# Educ-8.net
KiCad netlist of a schematic drawn in EAGLE
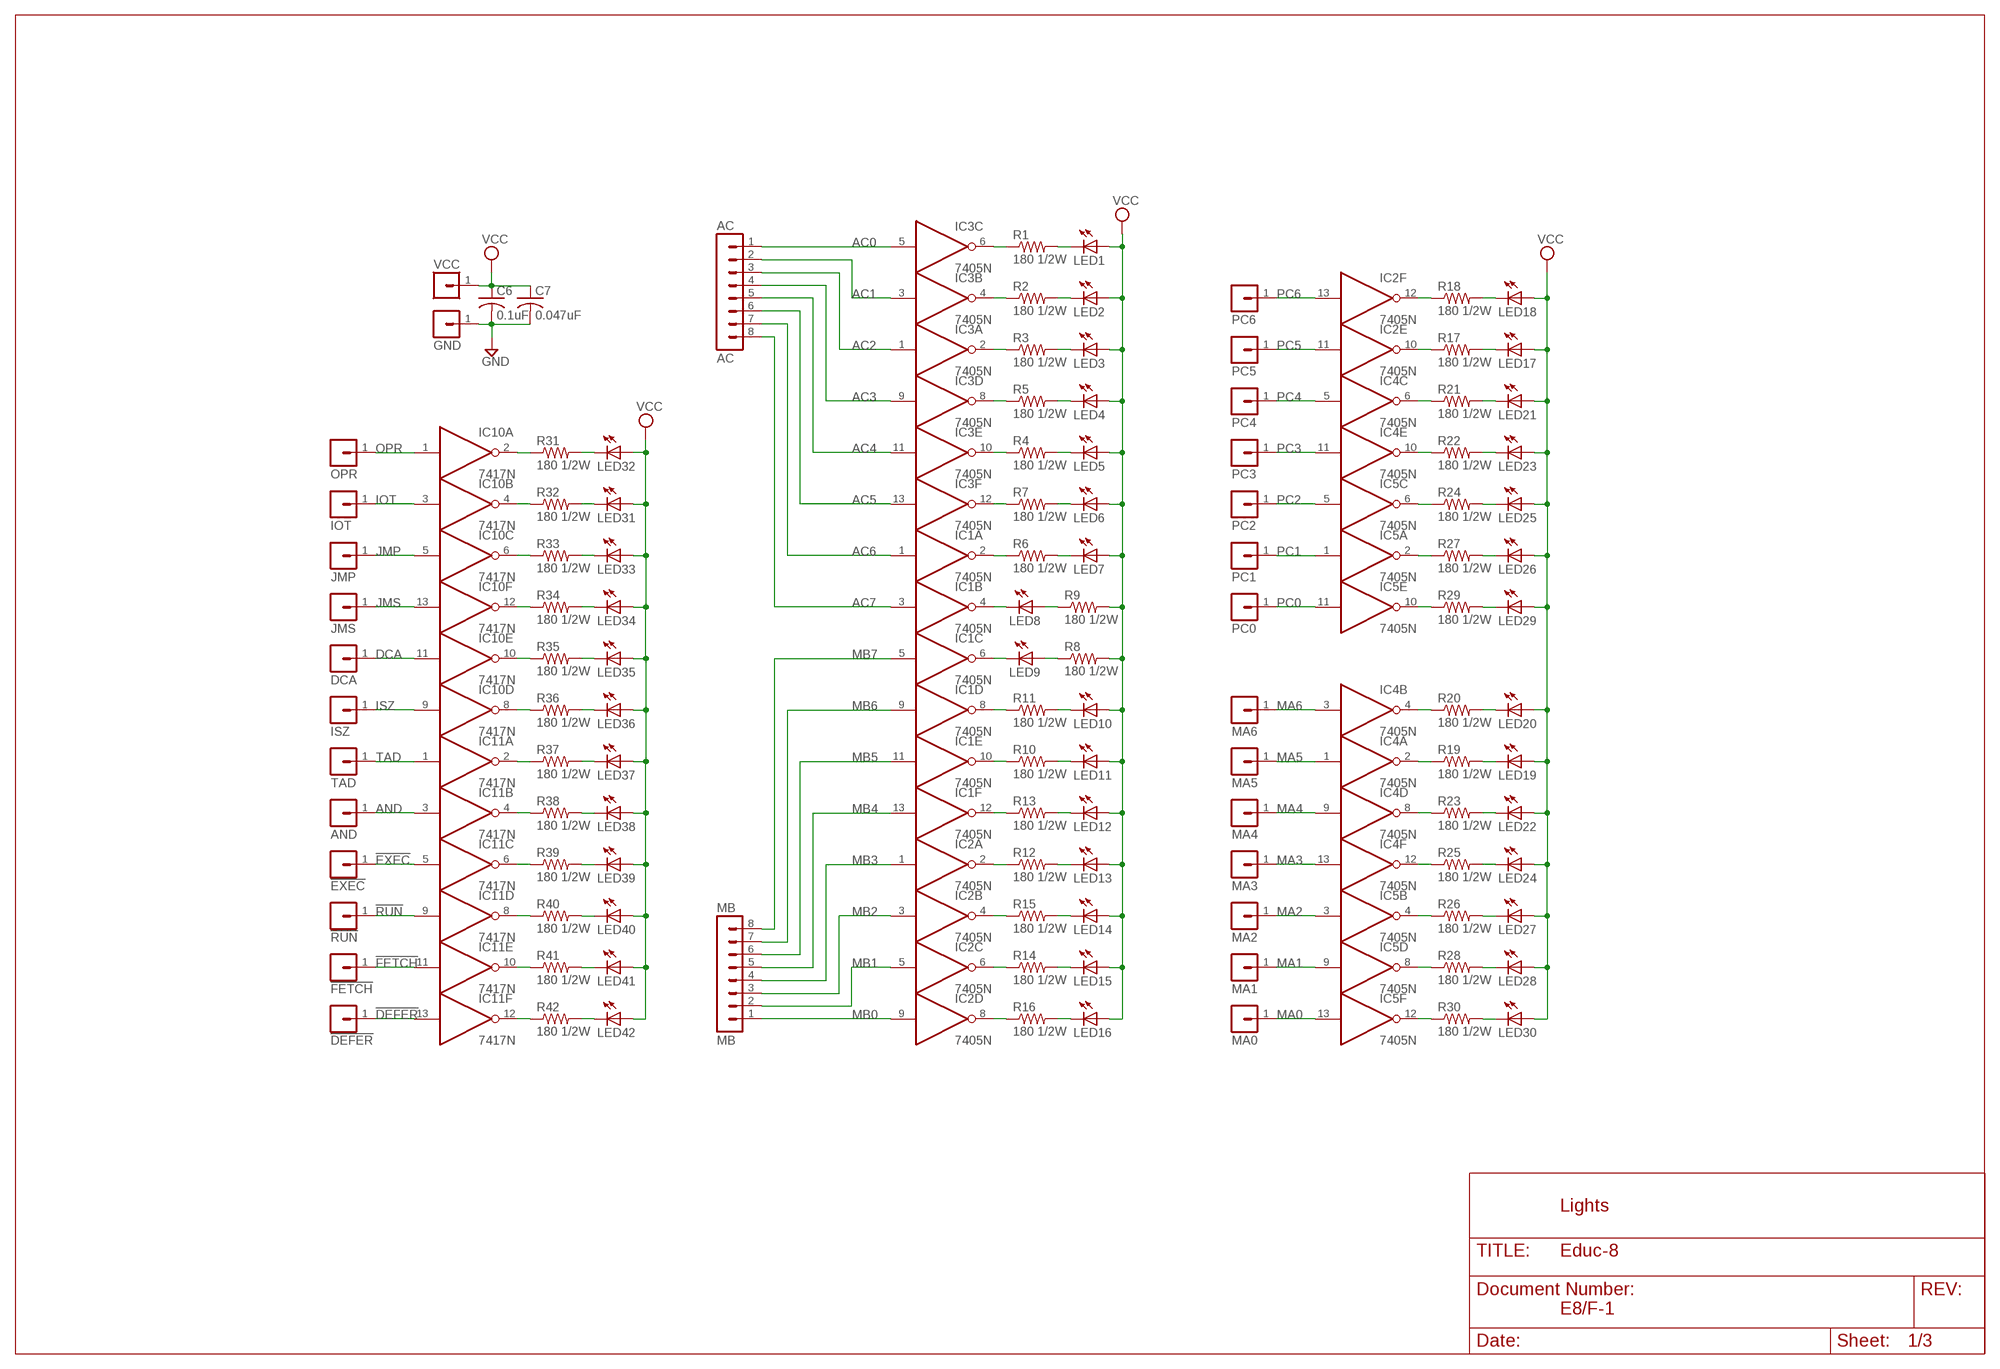
[diagram p0: schematic, sheet 1]
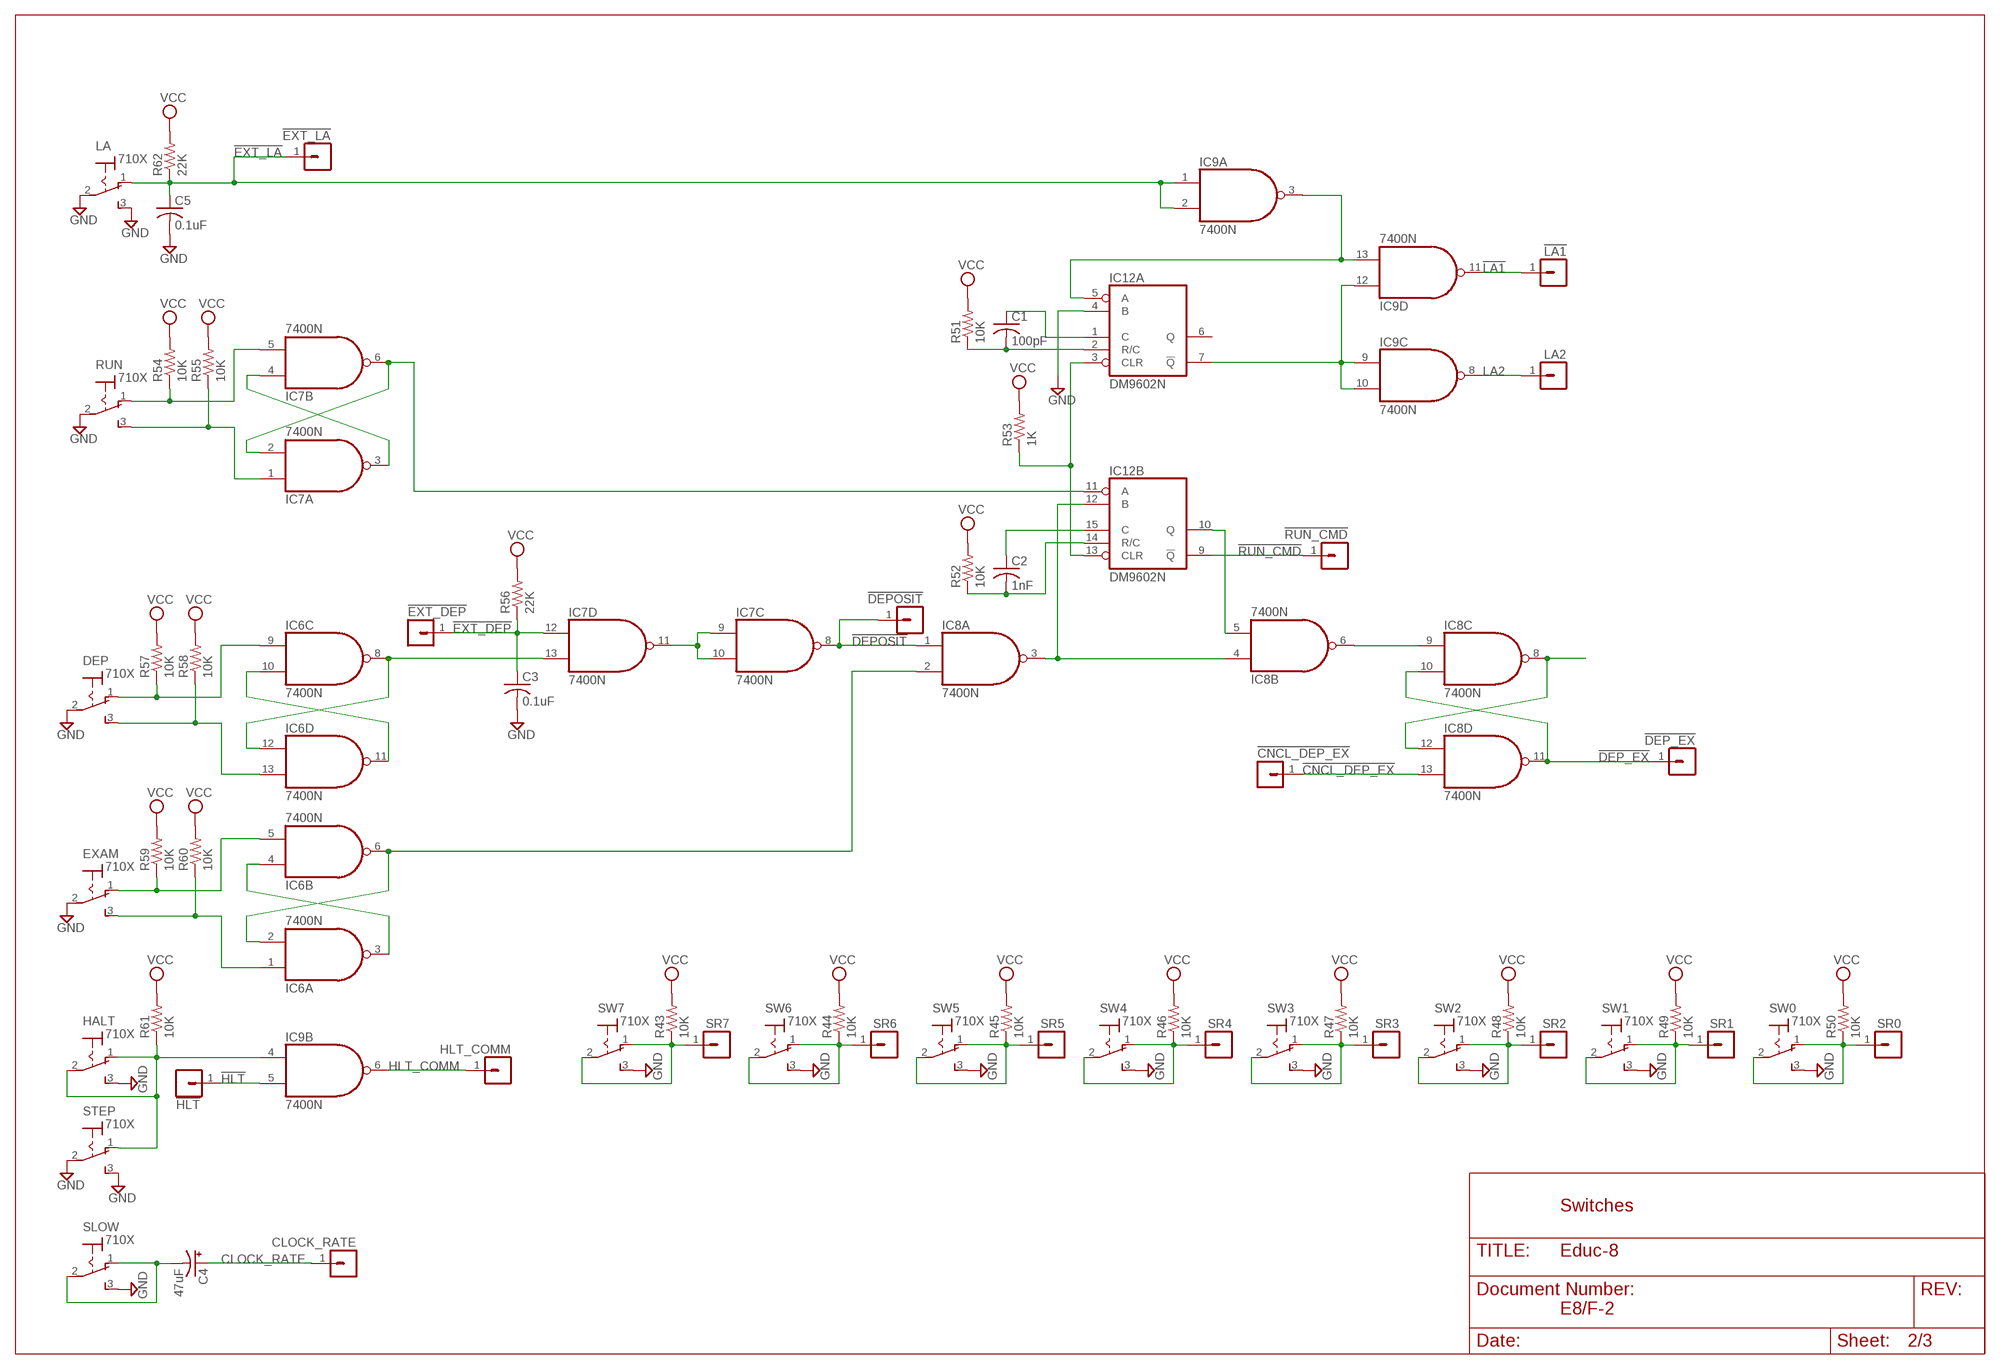
[diagram p1: schematic, sheet 2]
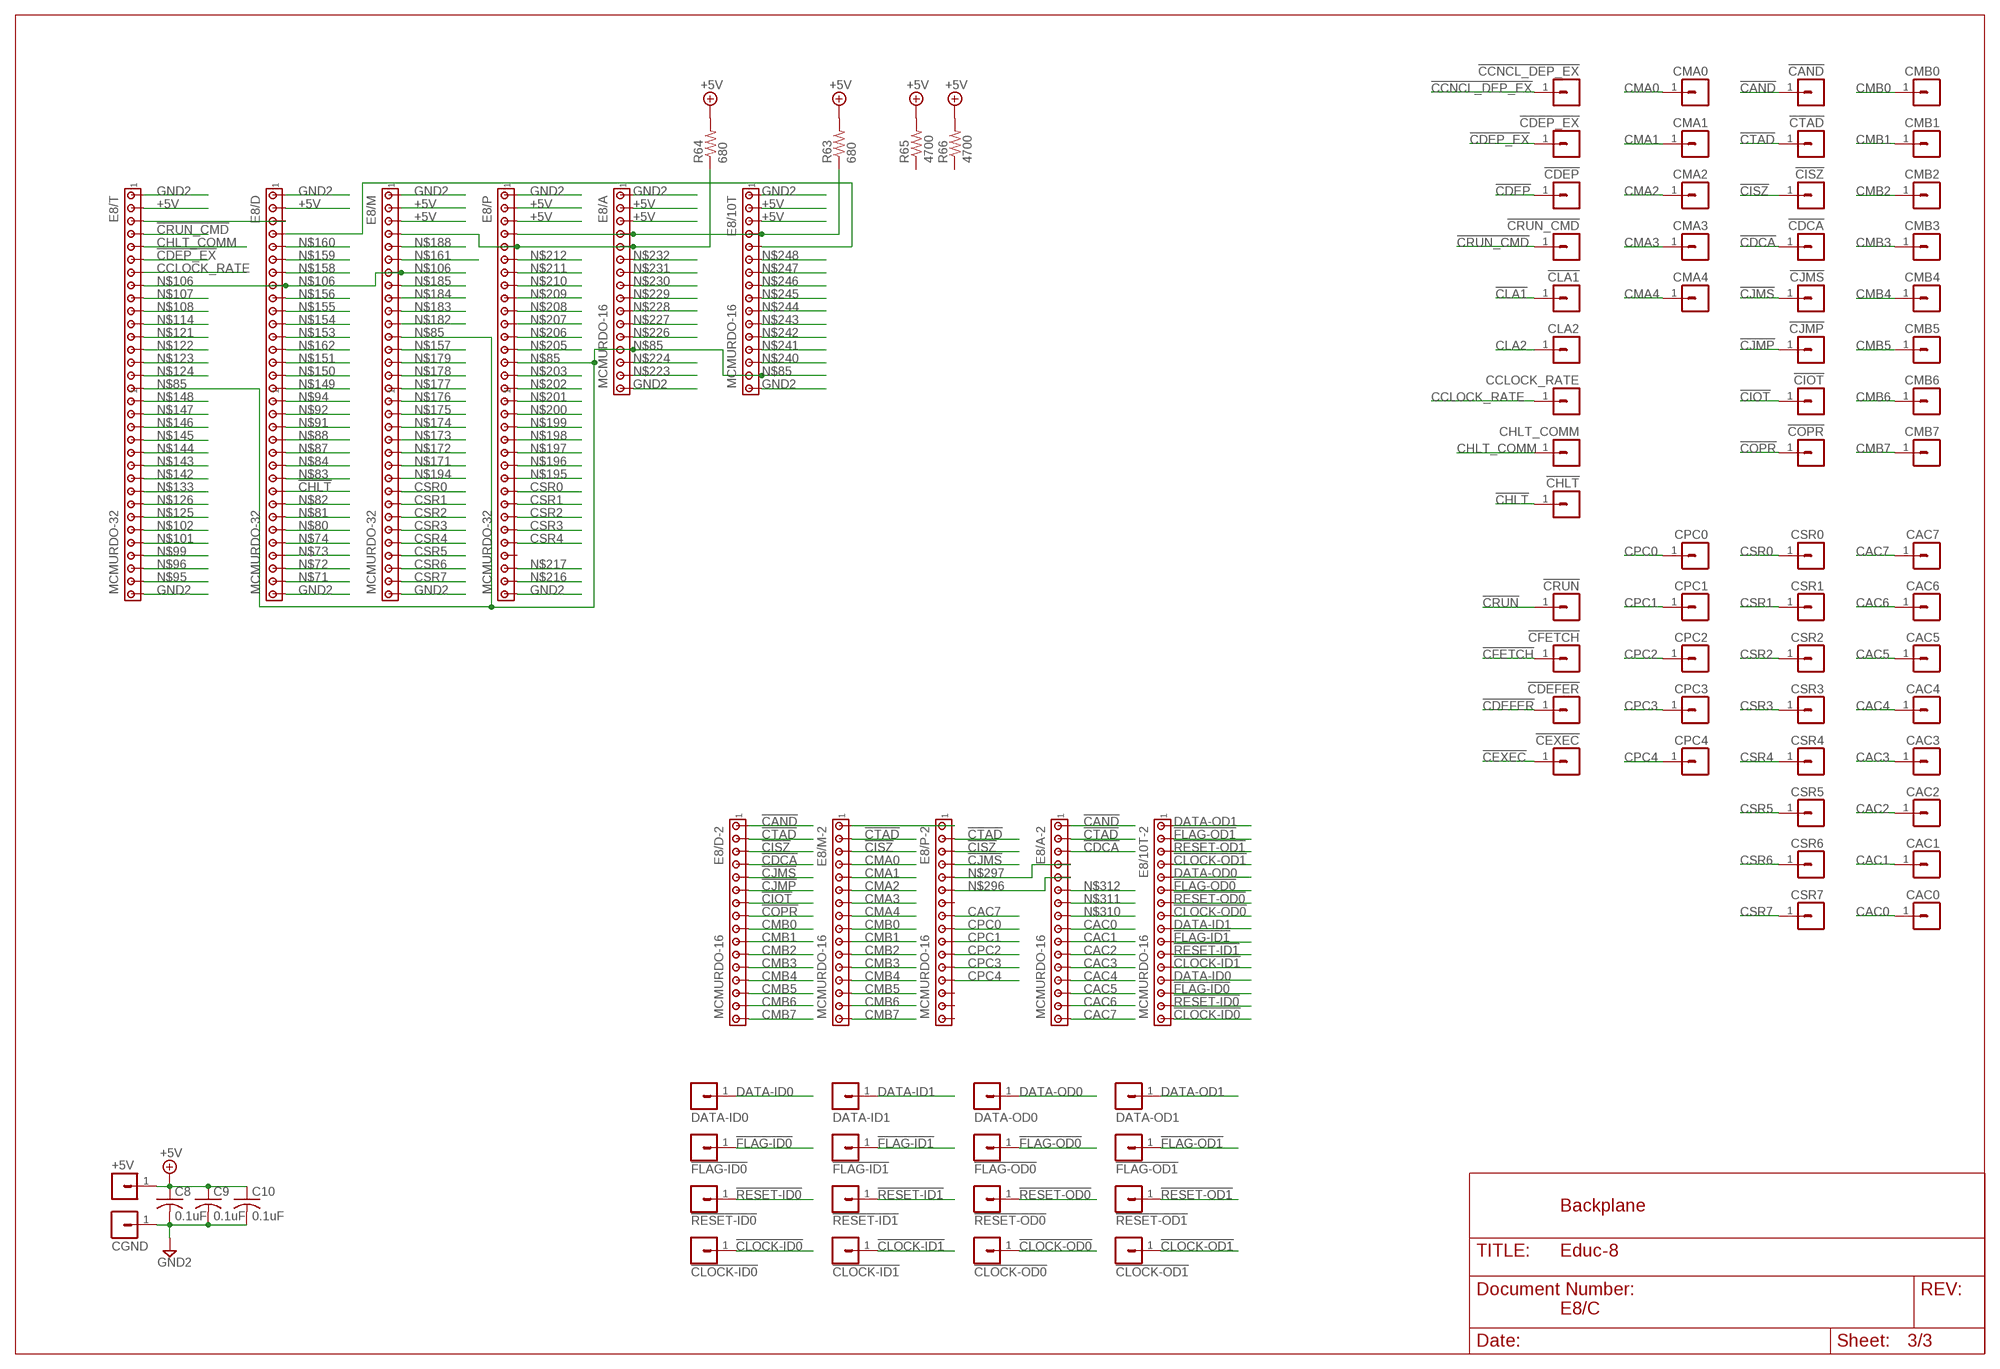
[diagram p2: schematic, sheet 3]

(export (version "E")
  (design (tool "Eeschema 10.0.6"))
  (components
    (comp (ref "!CNCL_DEP_EX")
      (value "MA01-1")
      (footprint "eagle-import:MA01-1")
      (libsource (lib "eagle-import") (part "MA01-1"))
    )
    (comp (ref "!DEPOSIT")
      (value "MA01-1")
      (footprint "eagle-import:MA01-1")
      (libsource (lib "eagle-import") (part "MA01-1"))
    )
    (comp (ref "!DEP_EX")
      (value "MA01-1")
      (footprint "eagle-import:MA01-1")
      (libsource (lib "eagle-import") (part "MA01-1"))
    )
    (comp (ref "!EXT_DEP")
      (value "MA01-1")
      (footprint "eagle-import:MA01-1")
      (libsource (lib "eagle-import") (part "MA01-1"))
    )
    (comp (ref "!EXT_LA")
      (value "MA01-1")
      (footprint "eagle-import:MA01-1")
      (libsource (lib "eagle-import") (part "MA01-1"))
    )
    (comp (ref "!HLT")
      (value "MA01-1")
      (footprint "eagle-import:MA01-1")
      (libsource (lib "eagle-import") (part "MA01-1"))
    )
    (comp (ref "!LA1")
      (value "MA01-1")
      (footprint "eagle-import:MA01-1")
      (libsource (lib "eagle-import") (part "MA01-1"))
    )
    (comp (ref "!RUN_CMD")
      (value "MA01-1")
      (footprint "eagle-import:MA01-1")
      (libsource (lib "eagle-import") (part "MA01-1"))
    )
    (comp (ref "C1")
      (value "100pF")
      (footprint "eagle-import:C075-032X103")
      (libsource (lib "eagle-import") (part "C-US075-032X103"))
    )
    (comp (ref "C2")
      (value "1nF")
      (footprint "eagle-import:C075-032X103")
      (libsource (lib "eagle-import") (part "C-US075-032X103"))
    )
    (comp (ref "C3")
      (value "0.1uF")
      (footprint "eagle-import:C063-025X075")
      (libsource (lib "eagle-import") (part "C-US"))
    )
    (comp (ref "C4")
      (value "47uF")
      (footprint "eagle-import:B45181C")
      (libsource (lib "eagle-import") (part "CPOL-USB45181C"))
    )
    (comp (ref "C5")
      (value "0.1uF")
      (footprint "eagle-import:C075-032X103")
      (libsource (lib "eagle-import") (part "C-US075-032X103"))
    )
    (comp (ref "CLOCK_RATE")
      (value "MA01-1")
      (footprint "eagle-import:MA01-1")
      (libsource (lib "eagle-import") (part "MA01-1"))
    )
    (comp (ref "DEP")
      (value "710X")
      (footprint "eagle-import:7109")
      (libsource (lib "eagle-import") (part "710X"))
    )
    (comp (ref "EXAM")
      (value "710X")
      (footprint "eagle-import:7109")
      (libsource (lib "eagle-import") (part "710X"))
    )
    (comp (ref "HALT")
      (value "710X")
      (footprint "eagle-import:7109")
      (libsource (lib "eagle-import") (part "710X"))
    )
    (comp (ref "HLT_COMM")
      (value "MA01-1")
      (footprint "eagle-import:MA01-1")
      (libsource (lib "eagle-import") (part "MA01-1"))
    )
    (comp (ref "IC6")
      (value "7400N")
      (footprint "eagle-import:DIL14")
      (libsource (lib "eagle-import") (part "7400N"))
    )
    (comp (ref "IC7")
      (value "7400N")
      (footprint "eagle-import:DIL14")
      (libsource (lib "eagle-import") (part "7400N"))
    )
    (comp (ref "IC8")
      (value "7400N")
      (footprint "eagle-import:DIL14")
      (libsource (lib "eagle-import") (part "7400N"))
    )
    (comp (ref "IC9")
      (value "7400N")
      (footprint "eagle-import:DIL14")
      (libsource (lib "eagle-import") (part "7400N"))
    )
    (comp (ref "IC12")
      (value "DM9602N")
      (footprint "eagle-import:DIL16")
      (libsource (lib "eagle-import") (part "DM9602N"))
    )
    (comp (ref "LA")
      (value "710X")
      (footprint "eagle-import:7109")
      (libsource (lib "eagle-import") (part "710X"))
    )
    (comp (ref "LA2")
      (value "MA01-1")
      (footprint "eagle-import:MA01-1")
      (libsource (lib "eagle-import") (part "MA01-1"))
    )
    (comp (ref "R43")
      (value "10K")
      (footprint "eagle-import:0207_12")
      (libsource (lib "eagle-import") (part "rcl_R-US_0207/12"))
    )
    (comp (ref "R44")
      (value "10K")
      (footprint "eagle-import:0207_12")
      (libsource (lib "eagle-import") (part "rcl_R-US_0207/12"))
    )
    (comp (ref "R45")
      (value "10K")
      (footprint "eagle-import:0207_12")
      (libsource (lib "eagle-import") (part "rcl_R-US_0207/12"))
    )
    (comp (ref "R46")
      (value "10K")
      (footprint "eagle-import:0207_12")
      (libsource (lib "eagle-import") (part "rcl_R-US_0207/12"))
    )
    (comp (ref "R47")
      (value "10K")
      (footprint "eagle-import:0207_12")
      (libsource (lib "eagle-import") (part "rcl_R-US_0207/12"))
    )
    (comp (ref "R48")
      (value "10K")
      (footprint "eagle-import:0207_12")
      (libsource (lib "eagle-import") (part "rcl_R-US_0207/12"))
    )
    (comp (ref "R49")
      (value "10K")
      (footprint "eagle-import:0207_12")
      (libsource (lib "eagle-import") (part "rcl_R-US_0207/12"))
    )
    (comp (ref "R50")
      (value "10K")
      (footprint "eagle-import:0207_12")
      (libsource (lib "eagle-import") (part "rcl_R-US_0207/12"))
    )
    (comp (ref "R51")
      (value "10K")
      (footprint "eagle-import:0207_10")
      (libsource (lib "eagle-import") (part "rcl_R-US_0207/10"))
    )
    (comp (ref "R52")
      (value "10K")
      (footprint "eagle-import:0207_15")
      (libsource (lib "eagle-import") (part "rcl_R-US_0207/15"))
    )
    (comp (ref "R53")
      (value "1K")
      (footprint "eagle-import:0204_6")
      (libsource (lib "eagle-import") (part "R-US_0204/6"))
    )
    (comp (ref "R54")
      (value "10K")
      (footprint "eagle-import:0207_13")
      (libsource (lib "eagle-import") (part "R-US_0207/13"))
    )
    (comp (ref "R55")
      (value "10K")
      (footprint "eagle-import:0207_13")
      (libsource (lib "eagle-import") (part "R-US_0207/13"))
    )
    (comp (ref "R56")
      (value "22K")
      (footprint "eagle-import:0207_10")
      (libsource (lib "eagle-import") (part "R-US_0207/10"))
    )
    (comp (ref "R57")
      (value "10K")
      (footprint "eagle-import:0207_13")
      (libsource (lib "eagle-import") (part "R-US_0207/13"))
    )
    (comp (ref "R58")
      (value "10K")
      (footprint "eagle-import:0207_13")
      (libsource (lib "eagle-import") (part "R-US_0207/13"))
    )
    (comp (ref "R59")
      (value "10K")
      (footprint "eagle-import:0207_13")
      (libsource (lib "eagle-import") (part "R-US_0207/13"))
    )
    (comp (ref "R60")
      (value "10K")
      (footprint "eagle-import:0207_13")
      (libsource (lib "eagle-import") (part "R-US_0207/13"))
    )
    (comp (ref "R61")
      (value "10K")
      (footprint "eagle-import:0207_22")
      (libsource (lib "eagle-import") (part "R-US_0207/22"))
    )
    (comp (ref "R62")
      (value "22K")
      (footprint "eagle-import:0207_13")
      (libsource (lib "eagle-import") (part "R-US_0207/13"))
    )
    (comp (ref "RUN")
      (value "710X")
      (footprint "eagle-import:7109")
      (libsource (lib "eagle-import") (part "710X"))
    )
    (comp (ref "SLOW")
      (value "710X")
      (footprint "eagle-import:7109")
      (libsource (lib "eagle-import") (part "710X"))
    )
    (comp (ref "SR0")
      (value "MA01-1")
      (footprint "eagle-import:MA01-1")
      (libsource (lib "eagle-import") (part "MA01-1"))
    )
    (comp (ref "SR1")
      (value "MA01-1")
      (footprint "eagle-import:MA01-1")
      (libsource (lib "eagle-import") (part "MA01-1"))
    )
    (comp (ref "SR2")
      (value "MA01-1")
      (footprint "eagle-import:MA01-1")
      (libsource (lib "eagle-import") (part "MA01-1"))
    )
    (comp (ref "SR3")
      (value "MA01-1")
      (footprint "eagle-import:MA01-1")
      (libsource (lib "eagle-import") (part "MA01-1"))
    )
    (comp (ref "SR4")
      (value "MA01-1")
      (footprint "eagle-import:MA01-1")
      (libsource (lib "eagle-import") (part "MA01-1"))
    )
    (comp (ref "SR5")
      (value "MA01-1")
      (footprint "eagle-import:MA01-1")
      (libsource (lib "eagle-import") (part "MA01-1"))
    )
    (comp (ref "SR6")
      (value "MA01-1")
      (footprint "eagle-import:MA01-1")
      (libsource (lib "eagle-import") (part "MA01-1"))
    )
    (comp (ref "SR7")
      (value "MA01-1")
      (footprint "eagle-import:MA01-1")
      (libsource (lib "eagle-import") (part "MA01-1"))
    )
    (comp (ref "STEP")
      (value "710X")
      (footprint "eagle-import:7109")
      (libsource (lib "eagle-import") (part "710X"))
    )
    (comp (ref "SW0")
      (value "710X")
      (footprint "eagle-import:7109")
      (libsource (lib "eagle-import") (part "710X"))
    )
    (comp (ref "SW1")
      (value "710X")
      (footprint "eagle-import:7109")
      (libsource (lib "eagle-import") (part "710X"))
    )
    (comp (ref "SW2")
      (value "710X")
      (footprint "eagle-import:7109")
      (libsource (lib "eagle-import") (part "710X"))
    )
    (comp (ref "SW3")
      (value "710X")
      (footprint "eagle-import:7109")
      (libsource (lib "eagle-import") (part "710X"))
    )
    (comp (ref "SW4")
      (value "710X")
      (footprint "eagle-import:7109")
      (libsource (lib "eagle-import") (part "710X"))
    )
    (comp (ref "SW5")
      (value "710X")
      (footprint "eagle-import:7109")
      (libsource (lib "eagle-import") (part "710X"))
    )
    (comp (ref "SW6")
      (value "710X")
      (footprint "eagle-import:7109")
      (libsource (lib "eagle-import") (part "710X"))
    )
    (comp (ref "SW7")
      (value "710X")
      (footprint "eagle-import:7109")
      (libsource (lib "eagle-import") (part "710X"))
    )
    (comp (ref "!DEFER")
      (value "MA01-1")
      (footprint "eagle-import:MA01-1")
      (libsource (lib "eagle-import") (part "MA01-1"))
    )
    (comp (ref "!EXEC")
      (value "MA01-1")
      (footprint "eagle-import:MA01-1")
      (libsource (lib "eagle-import") (part "MA01-1"))
    )
    (comp (ref "!FETCH")
      (value "MA01-1")
      (footprint "eagle-import:MA01-1")
      (libsource (lib "eagle-import") (part "MA01-1"))
    )
    (comp (ref "!RUN")
      (value "MA01-1")
      (footprint "eagle-import:MA01-1")
      (libsource (lib "eagle-import") (part "MA01-1"))
    )
    (comp (ref "AC")
      (value "AC")
      (footprint "eagle-import:MA08-1")
      (libsource (lib "eagle-import") (part "MA08-1"))
    )
    (comp (ref "AND")
      (value "MA01-1")
      (footprint "eagle-import:MA01-1")
      (libsource (lib "eagle-import") (part "MA01-1"))
    )
    (comp (ref "C6")
      (value "0.1uF")
      (footprint "eagle-import:C075-032X103")
      (libsource (lib "eagle-import") (part "C-US075-032X103"))
    )
    (comp (ref "C7")
      (value "0.047uF")
      (footprint "eagle-import:C075-032X103")
      (libsource (lib "eagle-import") (part "C-US075-032X103"))
    )
    (comp (ref "DCA")
      (value "MA01-1")
      (footprint "eagle-import:MA01-1")
      (libsource (lib "eagle-import") (part "MA01-1"))
    )
    (comp (ref "GND")
      (value "MA01-1")
      (footprint "eagle-import:MA01-1")
      (libsource (lib "eagle-import") (part "MA01-1"))
    )
    (comp (ref "IC1")
      (value "7405N")
      (footprint "eagle-import:DIL14")
      (libsource (lib "eagle-import") (part "7405N"))
    )
    (comp (ref "IC2")
      (value "7405N")
      (footprint "eagle-import:DIL14")
      (libsource (lib "eagle-import") (part "7405N"))
    )
    (comp (ref "IC3")
      (value "7405N")
      (footprint "eagle-import:DIL14")
      (libsource (lib "eagle-import") (part "7405N"))
    )
    (comp (ref "IC4")
      (value "7405N")
      (footprint "eagle-import:DIL14")
      (libsource (lib "eagle-import") (part "7405N"))
    )
    (comp (ref "IC5")
      (value "7405N")
      (footprint "eagle-import:DIL14")
      (libsource (lib "eagle-import") (part "7405N"))
    )
    (comp (ref "IC10")
      (value "7417N")
      (footprint "eagle-import:DIL14")
      (libsource (lib "eagle-import") (part "7417N"))
    )
    (comp (ref "IC11")
      (value "7417N")
      (footprint "eagle-import:DIL14")
      (libsource (lib "eagle-import") (part "7417N"))
    )
    (comp (ref "IOT")
      (value "MA01-1")
      (footprint "eagle-import:MA01-1")
      (libsource (lib "eagle-import") (part "MA01-1"))
    )
    (comp (ref "ISZ")
      (value "MA01-1")
      (footprint "eagle-import:MA01-1")
      (libsource (lib "eagle-import") (part "MA01-1"))
    )
    (comp (ref "JMP")
      (value "MA01-1")
      (footprint "eagle-import:MA01-1")
      (libsource (lib "eagle-import") (part "MA01-1"))
    )
    (comp (ref "JMS")
      (value "MA01-1")
      (footprint "eagle-import:MA01-1")
      (libsource (lib "eagle-import") (part "MA01-1"))
    )
    (comp (ref "LED1")
      (value "LED5MM")
      (footprint "eagle-import:LED5MM")
      (libsource (lib "eagle-import") (part "LED5MM"))
    )
    (comp (ref "LED2")
      (value "LED5MM")
      (footprint "eagle-import:LED5MM")
      (libsource (lib "eagle-import") (part "LED5MM"))
    )
    (comp (ref "LED3")
      (value "LED5MM")
      (footprint "eagle-import:LED5MM")
      (libsource (lib "eagle-import") (part "LED5MM"))
    )
    (comp (ref "LED4")
      (value "LED5MM")
      (footprint "eagle-import:LED5MM")
      (libsource (lib "eagle-import") (part "LED5MM"))
    )
    (comp (ref "LED5")
      (value "LED5MM")
      (footprint "eagle-import:LED5MM")
      (libsource (lib "eagle-import") (part "LED5MM"))
    )
    (comp (ref "LED6")
      (value "LED5MM")
      (footprint "eagle-import:LED5MM")
      (libsource (lib "eagle-import") (part "LED5MM"))
    )
    (comp (ref "LED7")
      (value "LED5MM")
      (footprint "eagle-import:LED5MM")
      (libsource (lib "eagle-import") (part "LED5MM"))
    )
    (comp (ref "LED8")
      (value "LED5MM")
      (footprint "eagle-import:LED5MM")
      (libsource (lib "eagle-import") (part "LED5MM"))
    )
    (comp (ref "LED9")
      (value "LED5MM")
      (footprint "eagle-import:LED5MM")
      (libsource (lib "eagle-import") (part "LED5MM"))
    )
    (comp (ref "LED10")
      (value "LED5MM")
      (footprint "eagle-import:LED5MM")
      (libsource (lib "eagle-import") (part "LED5MM"))
    )
    (comp (ref "LED11")
      (value "LED5MM")
      (footprint "eagle-import:LED5MM")
      (libsource (lib "eagle-import") (part "LED5MM"))
    )
    (comp (ref "LED12")
      (value "LED5MM")
      (footprint "eagle-import:LED5MM")
      (libsource (lib "eagle-import") (part "LED5MM"))
    )
    (comp (ref "LED13")
      (value "LED5MM")
      (footprint "eagle-import:LED5MM")
      (libsource (lib "eagle-import") (part "LED5MM"))
    )
    (comp (ref "LED14")
      (value "LED5MM")
      (footprint "eagle-import:LED5MM")
      (libsource (lib "eagle-import") (part "LED5MM"))
    )
    (comp (ref "LED15")
      (value "LED5MM")
      (footprint "eagle-import:LED5MM")
      (libsource (lib "eagle-import") (part "LED5MM"))
    )
    (comp (ref "LED16")
      (value "LED5MM")
      (footprint "eagle-import:LED5MM")
      (libsource (lib "eagle-import") (part "LED5MM"))
    )
    (comp (ref "LED17")
      (value "LED5MM")
      (footprint "eagle-import:LED5MM")
      (libsource (lib "eagle-import") (part "LED5MM"))
    )
    (comp (ref "LED18")
      (value "LED5MM")
      (footprint "eagle-import:LED5MM")
      (libsource (lib "eagle-import") (part "LED5MM"))
    )
    (comp (ref "LED19")
      (value "LED5MM")
      (footprint "eagle-import:LED5MM")
      (libsource (lib "eagle-import") (part "LED5MM"))
    )
    (comp (ref "LED20")
      (value "LED5MM")
      (footprint "eagle-import:LED5MM")
      (libsource (lib "eagle-import") (part "LED5MM"))
    )
    (comp (ref "LED21")
      (value "LED5MM")
      (footprint "eagle-import:LED5MM")
      (libsource (lib "eagle-import") (part "LED5MM"))
    )
    (comp (ref "LED22")
      (value "LED5MM")
      (footprint "eagle-import:LED5MM")
      (libsource (lib "eagle-import") (part "LED5MM"))
    )
    (comp (ref "LED23")
      (value "LED5MM")
      (footprint "eagle-import:LED5MM")
      (libsource (lib "eagle-import") (part "LED5MM"))
    )
    (comp (ref "LED24")
      (value "LED5MM")
      (footprint "eagle-import:LED5MM")
      (libsource (lib "eagle-import") (part "LED5MM"))
    )
    (comp (ref "LED25")
      (value "LED5MM")
      (footprint "eagle-import:LED5MM")
      (libsource (lib "eagle-import") (part "LED5MM"))
    )
    (comp (ref "LED26")
      (value "LED5MM")
      (footprint "eagle-import:LED5MM")
      (libsource (lib "eagle-import") (part "LED5MM"))
    )
    (comp (ref "LED27")
      (value "LED5MM")
      (footprint "eagle-import:LED5MM")
      (libsource (lib "eagle-import") (part "LED5MM"))
    )
    (comp (ref "LED28")
      (value "LED5MM")
      (footprint "eagle-import:LED5MM")
      (libsource (lib "eagle-import") (part "LED5MM"))
    )
    (comp (ref "LED29")
      (value "LED5MM")
      (footprint "eagle-import:LED5MM")
      (libsource (lib "eagle-import") (part "LED5MM"))
    )
    (comp (ref "LED30")
      (value "LED5MM")
      (footprint "eagle-import:LED5MM")
      (libsource (lib "eagle-import") (part "LED5MM"))
    )
    (comp (ref "LED31")
      (value "LED5MM")
      (footprint "eagle-import:LED5MM")
      (libsource (lib "eagle-import") (part "LED5MM"))
    )
    (comp (ref "LED32")
      (value "LED5MM")
      (footprint "eagle-import:LED5MM")
      (libsource (lib "eagle-import") (part "LED5MM"))
    )
    (comp (ref "LED33")
      (value "LED5MM")
      (footprint "eagle-import:LED5MM")
      (libsource (lib "eagle-import") (part "LED5MM"))
    )
    (comp (ref "LED34")
      (value "LED5MM")
      (footprint "eagle-import:LED5MM")
      (libsource (lib "eagle-import") (part "LED5MM"))
    )
    (comp (ref "LED35")
      (value "LED5MM")
      (footprint "eagle-import:LED5MM")
      (libsource (lib "eagle-import") (part "LED5MM"))
    )
    (comp (ref "LED36")
      (value "LED5MM")
      (footprint "eagle-import:LED5MM")
      (libsource (lib "eagle-import") (part "LED5MM"))
    )
    (comp (ref "LED37")
      (value "LED5MM")
      (footprint "eagle-import:LED5MM")
      (libsource (lib "eagle-import") (part "LED5MM"))
    )
    (comp (ref "LED38")
      (value "LED5MM")
      (footprint "eagle-import:LED5MM")
      (libsource (lib "eagle-import") (part "LED5MM"))
    )
    (comp (ref "LED39")
      (value "LED5MM")
      (footprint "eagle-import:LED5MM")
      (libsource (lib "eagle-import") (part "LED5MM"))
    )
    (comp (ref "LED40")
      (value "LED5MM")
      (footprint "eagle-import:LED5MM")
      (libsource (lib "eagle-import") (part "LED5MM"))
    )
    (comp (ref "LED41")
      (value "LED5MM")
      (footprint "eagle-import:LED5MM")
      (libsource (lib "eagle-import") (part "LED5MM"))
    )
    (comp (ref "LED42")
      (value "LED5MM")
      (footprint "eagle-import:LED5MM")
      (libsource (lib "eagle-import") (part "LED5MM"))
    )
    (comp (ref "MA0")
      (value "MA01-1")
      (footprint "eagle-import:MA01-1")
      (libsource (lib "eagle-import") (part "MA01-1"))
    )
    (comp (ref "MA1")
      (value "MA01-1")
      (footprint "eagle-import:MA01-1")
      (libsource (lib "eagle-import") (part "MA01-1"))
    )
    (comp (ref "MA2")
      (value "MA01-1")
      (footprint "eagle-import:MA01-1")
      (libsource (lib "eagle-import") (part "MA01-1"))
    )
    (comp (ref "MA3")
      (value "MA01-1")
      (footprint "eagle-import:MA01-1")
      (libsource (lib "eagle-import") (part "MA01-1"))
    )
    (comp (ref "MA4")
      (value "MA01-1")
      (footprint "eagle-import:MA01-1")
      (libsource (lib "eagle-import") (part "MA01-1"))
    )
    (comp (ref "MA5")
      (value "MA01-1")
      (footprint "eagle-import:MA01-1")
      (libsource (lib "eagle-import") (part "MA01-1"))
    )
    (comp (ref "MA6")
      (value "MA01-1")
      (footprint "eagle-import:MA01-1")
      (libsource (lib "eagle-import") (part "MA01-1"))
    )
    (comp (ref "MB")
      (value "MB")
      (footprint "eagle-import:MA08-1")
      (libsource (lib "eagle-import") (part "MA08-1"))
    )
    (comp (ref "OPR")
      (value "MA01-1")
      (footprint "eagle-import:MA01-1")
      (libsource (lib "eagle-import") (part "MA01-1"))
    )
    (comp (ref "PC0")
      (value "MA01-1")
      (footprint "eagle-import:MA01-1")
      (libsource (lib "eagle-import") (part "MA01-1"))
    )
    (comp (ref "PC1")
      (value "MA01-1")
      (footprint "eagle-import:MA01-1")
      (libsource (lib "eagle-import") (part "MA01-1"))
    )
    (comp (ref "PC2")
      (value "MA01-1")
      (footprint "eagle-import:MA01-1")
      (libsource (lib "eagle-import") (part "MA01-1"))
    )
    (comp (ref "PC3")
      (value "MA01-1")
      (footprint "eagle-import:MA01-1")
      (libsource (lib "eagle-import") (part "MA01-1"))
    )
    (comp (ref "PC4")
      (value "MA01-1")
      (footprint "eagle-import:MA01-1")
      (libsource (lib "eagle-import") (part "MA01-1"))
    )
    (comp (ref "PC5")
      (value "MA01-1")
      (footprint "eagle-import:MA01-1")
      (libsource (lib "eagle-import") (part "MA01-1"))
    )
    (comp (ref "PC6")
      (value "MA01-1")
      (footprint "eagle-import:MA01-1")
      (libsource (lib "eagle-import") (part "MA01-1"))
    )
    (comp (ref "R1")
      (value "180 1/2W")
      (footprint "eagle-import:0309_.45")
      (libsource (lib "eagle-import") (part "R-US_0309/.45"))
    )
    (comp (ref "R2")
      (value "180 1/2W")
      (footprint "eagle-import:0309_.45")
      (libsource (lib "eagle-import") (part "R-US_0309/.45"))
    )
    (comp (ref "R3")
      (value "180 1/2W")
      (footprint "eagle-import:0309_.45")
      (libsource (lib "eagle-import") (part "R-US_0309/.45"))
    )
    (comp (ref "R4")
      (value "180 1/2W")
      (footprint "eagle-import:0309_12")
      (libsource (lib "eagle-import") (part "rcl_R-US_0309/12"))
    )
    (comp (ref "R5")
      (value "180 1/2W")
      (footprint "eagle-import:0309_.45")
      (libsource (lib "eagle-import") (part "R-US_0309/.45"))
    )
    (comp (ref "R6")
      (value "180 1/2W")
      (footprint "eagle-import:0309_12")
      (libsource (lib "eagle-import") (part "rcl_R-US_0309/12"))
    )
    (comp (ref "R7")
      (value "180 1/2W")
      (footprint "eagle-import:0309_.45")
      (libsource (lib "eagle-import") (part "R-US_0309/.45"))
    )
    (comp (ref "R8")
      (value "180 1/2W")
      (footprint "eagle-import:0309_12")
      (libsource (lib "eagle-import") (part "rcl_R-US_0309/12"))
    )
    (comp (ref "R9")
      (value "180 1/2W")
      (footprint "eagle-import:0309_12")
      (libsource (lib "eagle-import") (part "rcl_R-US_0309/12"))
    )
    (comp (ref "R10")
      (value "180 1/2W")
      (footprint "eagle-import:0309_.45")
      (libsource (lib "eagle-import") (part "R-US_0309/.45"))
    )
    (comp (ref "R11")
      (value "180 1/2W")
      (footprint "eagle-import:0309_11")
      (libsource (lib "eagle-import") (part "R-US_0309/11"))
    )
    (comp (ref "R12")
      (value "180 1/2W")
      (footprint "eagle-import:0309_12")
      (libsource (lib "eagle-import") (part "rcl_R-US_0309/12"))
    )
    (comp (ref "R13")
      (value "180 1/2W")
      (footprint "eagle-import:0309_.45")
      (libsource (lib "eagle-import") (part "R-US_0309/.45"))
    )
    (comp (ref "R14")
      (value "180 1/2W")
      (footprint "eagle-import:0309_.45")
      (libsource (lib "eagle-import") (part "R-US_0309/.45"))
    )
    (comp (ref "R15")
      (value "180 1/2W")
      (footprint "eagle-import:0309_12")
      (libsource (lib "eagle-import") (part "rcl_R-US_0309/12"))
    )
    (comp (ref "R16")
      (value "180 1/2W")
      (footprint "eagle-import:0309_12")
      (libsource (lib "eagle-import") (part "rcl_R-US_0309/12"))
    )
    (comp (ref "R17")
      (value "180 1/2W")
      (footprint "eagle-import:0309_12")
      (libsource (lib "eagle-import") (part "rcl_R-US_0309/12"))
    )
    (comp (ref "R18")
      (value "180 1/2W")
      (footprint "eagle-import:0309_12")
      (libsource (lib "eagle-import") (part "rcl_R-US_0309/12"))
    )
    (comp (ref "R19")
      (value "180 1/2W")
      (footprint "eagle-import:0309_12")
      (libsource (lib "eagle-import") (part "R-US_0309/12"))
    )
    (comp (ref "R20")
      (value "180 1/2W")
      (footprint "eagle-import:0309_15")
      (libsource (lib "eagle-import") (part "R-US_0309/15"))
    )
    (comp (ref "R21")
      (value "180 1/2W")
      (footprint "eagle-import:0309_.45")
      (libsource (lib "eagle-import") (part "R-US_0309/.45"))
    )
    (comp (ref "R22")
      (value "180 1/2W")
      (footprint "eagle-import:0309_10")
      (libsource (lib "eagle-import") (part "R-US_0309/10"))
    )
    (comp (ref "R23")
      (value "180 1/2W")
      (footprint "eagle-import:0309_10")
      (libsource (lib "eagle-import") (part "rcl_R-US_0309/10"))
    )
    (comp (ref "R24")
      (value "180 1/2W")
      (footprint "eagle-import:0309_12")
      (libsource (lib "eagle-import") (part "rcl_R-US_0309/12"))
    )
    (comp (ref "R25")
      (value "180 1/2W")
      (footprint "eagle-import:0309_10")
      (libsource (lib "eagle-import") (part "rcl_R-US_0309/10"))
    )
    (comp (ref "R26")
      (value "180 1/2W")
      (footprint "eagle-import:0309_10")
      (libsource (lib "eagle-import") (part "R-US_0309/10"))
    )
    (comp (ref "R27")
      (value "180 1/2W")
      (footprint "eagle-import:0309_15")
      (libsource (lib "eagle-import") (part "R-US_0309/15"))
    )
    (comp (ref "R28")
      (value "180 1/2W")
      (footprint "eagle-import:0309_.45")
      (libsource (lib "eagle-import") (part "R-US_0309/.45"))
    )
    (comp (ref "R29")
      (value "180 1/2W")
      (footprint "eagle-import:0309_.45")
      (libsource (lib "eagle-import") (part "R-US_0309/.45"))
    )
    (comp (ref "R30")
      (value "180 1/2W")
      (footprint "eagle-import:0309_.45")
      (libsource (lib "eagle-import") (part "R-US_0309/.45"))
    )
    (comp (ref "R31")
      (value "180 1/2W")
      (footprint "eagle-import:0309_8")
      (libsource (lib "eagle-import") (part "R-US_0309/8"))
    )
    (comp (ref "R32")
      (value "180 1/2W")
      (footprint "eagle-import:0309_8")
      (libsource (lib "eagle-import") (part "R-US_0309/8"))
    )
    (comp (ref "R33")
      (value "180 1/2W")
      (footprint "eagle-import:0309_8")
      (libsource (lib "eagle-import") (part "R-US_0309/8"))
    )
    (comp (ref "R34")
      (value "180 1/2W")
      (footprint "eagle-import:0309_8")
      (libsource (lib "eagle-import") (part "R-US_0309/8"))
    )
    (comp (ref "R35")
      (value "180 1/2W")
      (footprint "eagle-import:0309_8")
      (libsource (lib "eagle-import") (part "R-US_0309/8"))
    )
    (comp (ref "R36")
      (value "180 1/2W")
      (footprint "eagle-import:0309_8")
      (libsource (lib "eagle-import") (part "R-US_0309/8"))
    )
    (comp (ref "R37")
      (value "180 1/2W")
      (footprint "eagle-import:0309_8")
      (libsource (lib "eagle-import") (part "R-US_0309/8"))
    )
    (comp (ref "R38")
      (value "180 1/2W")
      (footprint "eagle-import:0309_8")
      (libsource (lib "eagle-import") (part "R-US_0309/8"))
    )
    (comp (ref "R39")
      (value "180 1/2W")
      (footprint "eagle-import:0309_10")
      (libsource (lib "eagle-import") (part "R-US_0309/10"))
    )
    (comp (ref "R40")
      (value "180 1/2W")
      (footprint "eagle-import:0309_10")
      (libsource (lib "eagle-import") (part "R-US_0309/10"))
    )
    (comp (ref "R41")
      (value "180 1/2W")
      (footprint "eagle-import:0309_10")
      (libsource (lib "eagle-import") (part "R-US_0309/10"))
    )
    (comp (ref "R42")
      (value "180 1/2W")
      (footprint "eagle-import:0309_10")
      (libsource (lib "eagle-import") (part "R-US_0309/10"))
    )
    (comp (ref "TAD")
      (value "MA01-1")
      (footprint "eagle-import:MA01-1")
      (libsource (lib "eagle-import") (part "MA01-1"))
    )
    (comp (ref "VCC")
      (value "MA01-1")
      (footprint "eagle-import:MA01-1")
      (libsource (lib "eagle-import") (part "MA01-1"))
    )
    (comp (ref "!CAND")
      (value "MA01-1")
      (footprint "eagle-import:MA01-1")
      (libsource (lib "eagle-import") (part "MA01-1"))
    )
    (comp (ref "!CCNCL_DEP_EX")
      (value "MA01-1")
      (footprint "eagle-import:MA01-1")
      (libsource (lib "eagle-import") (part "MA01-1"))
    )
    (comp (ref "!CDCA")
      (value "MA01-1")
      (footprint "eagle-import:MA01-1")
      (libsource (lib "eagle-import") (part "MA01-1"))
    )
    (comp (ref "!CDEFER")
      (value "MA01-1")
      (footprint "eagle-import:MA01-1")
      (libsource (lib "eagle-import") (part "MA01-1"))
    )
    (comp (ref "!CDEP")
      (value "MA01-1")
      (footprint "eagle-import:MA01-1")
      (libsource (lib "eagle-import") (part "MA01-1"))
    )
    (comp (ref "!CDEP_EX")
      (value "MA01-1")
      (footprint "eagle-import:MA01-1")
      (libsource (lib "eagle-import") (part "MA01-1"))
    )
    (comp (ref "!CEXEC")
      (value "MA01-1")
      (footprint "eagle-import:MA01-1")
      (libsource (lib "eagle-import") (part "MA01-1"))
    )
    (comp (ref "!CFETCH")
      (value "MA01-1")
      (footprint "eagle-import:MA01-1")
      (libsource (lib "eagle-import") (part "MA01-1"))
    )
    (comp (ref "!CHLT")
      (value "MA01-1")
      (footprint "eagle-import:MA01-1")
      (libsource (lib "eagle-import") (part "MA01-1"))
    )
    (comp (ref "!CIOT")
      (value "MA01-1")
      (footprint "eagle-import:MA01-1")
      (libsource (lib "eagle-import") (part "MA01-1"))
    )
    (comp (ref "!CISZ")
      (value "MA01-1")
      (footprint "eagle-import:MA01-1")
      (libsource (lib "eagle-import") (part "MA01-1"))
    )
    (comp (ref "!CJMP")
      (value "MA01-1")
      (footprint "eagle-import:MA01-1")
      (libsource (lib "eagle-import") (part "MA01-1"))
    )
    (comp (ref "!CJMS")
      (value "MA01-1")
      (footprint "eagle-import:MA01-1")
      (libsource (lib "eagle-import") (part "MA01-1"))
    )
    (comp (ref "!CLA1")
      (value "MA01-1")
      (footprint "eagle-import:MA01-1")
      (libsource (lib "eagle-import") (part "MA01-1"))
    )
    (comp (ref "!CLOCK-ID0")
      (value "MA01-1")
      (footprint "eagle-import:MA01-1")
      (libsource (lib "eagle-import") (part "MA01-1"))
    )
    (comp (ref "!CLOCK-ID1")
      (value "MA01-1")
      (footprint "eagle-import:MA01-1")
      (libsource (lib "eagle-import") (part "MA01-1"))
    )
    (comp (ref "!CLOCK-OD0")
      (value "MA01-1")
      (footprint "eagle-import:MA01-1")
      (libsource (lib "eagle-import") (part "MA01-1"))
    )
    (comp (ref "!CLOCK-OD1")
      (value "MA01-1")
      (footprint "eagle-import:MA01-1")
      (libsource (lib "eagle-import") (part "MA01-1"))
    )
    (comp (ref "!COPR")
      (value "MA01-1")
      (footprint "eagle-import:MA01-1")
      (libsource (lib "eagle-import") (part "MA01-1"))
    )
    (comp (ref "!CRUN")
      (value "MA01-1")
      (footprint "eagle-import:MA01-1")
      (libsource (lib "eagle-import") (part "MA01-1"))
    )
    (comp (ref "!CRUN_CMD")
      (value "MA01-1")
      (footprint "eagle-import:MA01-1")
      (libsource (lib "eagle-import") (part "MA01-1"))
    )
    (comp (ref "!CTAD")
      (value "MA01-1")
      (footprint "eagle-import:MA01-1")
      (libsource (lib "eagle-import") (part "MA01-1"))
    )
    (comp (ref "!FLAG-ID0")
      (value "MA01-1")
      (footprint "eagle-import:MA01-1")
      (libsource (lib "eagle-import") (part "MA01-1"))
    )
    (comp (ref "!FLAG-ID1")
      (value "MA01-1")
      (footprint "eagle-import:MA01-1")
      (libsource (lib "eagle-import") (part "MA01-1"))
    )
    (comp (ref "!FLAG-OD0")
      (value "MA01-1")
      (footprint "eagle-import:MA01-1")
      (libsource (lib "eagle-import") (part "MA01-1"))
    )
    (comp (ref "!FLAG-OD1")
      (value "MA01-1")
      (footprint "eagle-import:MA01-1")
      (libsource (lib "eagle-import") (part "MA01-1"))
    )
    (comp (ref "!RESET-ID0")
      (value "MA01-1")
      (footprint "eagle-import:MA01-1")
      (libsource (lib "eagle-import") (part "MA01-1"))
    )
    (comp (ref "!RESET-ID1")
      (value "MA01-1")
      (footprint "eagle-import:MA01-1")
      (libsource (lib "eagle-import") (part "MA01-1"))
    )
    (comp (ref "!RESET-OD0")
      (value "MA01-1")
      (footprint "eagle-import:MA01-1")
      (libsource (lib "eagle-import") (part "MA01-1"))
    )
    (comp (ref "!RESET-OD1")
      (value "MA01-1")
      (footprint "eagle-import:MA01-1")
      (libsource (lib "eagle-import") (part "MA01-1"))
    )
    (comp (ref "+5V")
      (value "MA01-1")
      (footprint "eagle-import:MA01-1")
      (libsource (lib "eagle-import") (part "MA01-1"))
    )
    (comp (ref "C8")
      (value "0.1uF")
      (footprint "eagle-import:C075-032X103")
      (libsource (lib "eagle-import") (part "C-US075-032X103"))
    )
    (comp (ref "C9")
      (value "0.1uF")
      (footprint "eagle-import:C075-032X103")
      (libsource (lib "eagle-import") (part "C-US075-032X103"))
    )
    (comp (ref "C10")
      (value "0.1uF")
      (footprint "eagle-import:C075-032X103")
      (libsource (lib "eagle-import") (part "C-US075-032X103"))
    )
    (comp (ref "CAC0")
      (value "MA01-1")
      (footprint "eagle-import:MA01-1")
      (libsource (lib "eagle-import") (part "MA01-1"))
    )
    (comp (ref "CAC1")
      (value "MA01-1")
      (footprint "eagle-import:MA01-1")
      (libsource (lib "eagle-import") (part "MA01-1"))
    )
    (comp (ref "CAC2")
      (value "MA01-1")
      (footprint "eagle-import:MA01-1")
      (libsource (lib "eagle-import") (part "MA01-1"))
    )
    (comp (ref "CAC3")
      (value "MA01-1")
      (footprint "eagle-import:MA01-1")
      (libsource (lib "eagle-import") (part "MA01-1"))
    )
    (comp (ref "CAC4")
      (value "MA01-1")
      (footprint "eagle-import:MA01-1")
      (libsource (lib "eagle-import") (part "MA01-1"))
    )
    (comp (ref "CAC5")
      (value "MA01-1")
      (footprint "eagle-import:MA01-1")
      (libsource (lib "eagle-import") (part "MA01-1"))
    )
    (comp (ref "CAC6")
      (value "MA01-1")
      (footprint "eagle-import:MA01-1")
      (libsource (lib "eagle-import") (part "MA01-1"))
    )
    (comp (ref "CAC7")
      (value "MA01-1")
      (footprint "eagle-import:MA01-1")
      (libsource (lib "eagle-import") (part "MA01-1"))
    )
    (comp (ref "CCLOCK_RATE")
      (value "MA01-1")
      (footprint "eagle-import:MA01-1")
      (libsource (lib "eagle-import") (part "MA01-1"))
    )
    (comp (ref "CGND")
      (value "MA01-1")
      (footprint "eagle-import:MA01-1")
      (libsource (lib "eagle-import") (part "MA01-1"))
    )
    (comp (ref "CHLT_COMM")
      (value "MA01-1")
      (footprint "eagle-import:MA01-1")
      (libsource (lib "eagle-import") (part "MA01-1"))
    )
    (comp (ref "CLA2")
      (value "MA01-1")
      (footprint "eagle-import:MA01-1")
      (libsource (lib "eagle-import") (part "MA01-1"))
    )
    (comp (ref "CMA0")
      (value "MA01-1")
      (footprint "eagle-import:MA01-1")
      (libsource (lib "eagle-import") (part "MA01-1"))
    )
    (comp (ref "CMA1")
      (value "MA01-1")
      (footprint "eagle-import:MA01-1")
      (libsource (lib "eagle-import") (part "MA01-1"))
    )
    (comp (ref "CMA2")
      (value "MA01-1")
      (footprint "eagle-import:MA01-1")
      (libsource (lib "eagle-import") (part "MA01-1"))
    )
    (comp (ref "CMA3")
      (value "MA01-1")
      (footprint "eagle-import:MA01-1")
      (libsource (lib "eagle-import") (part "MA01-1"))
    )
    (comp (ref "CMA4")
      (value "MA01-1")
      (footprint "eagle-import:MA01-1")
      (libsource (lib "eagle-import") (part "MA01-1"))
    )
    (comp (ref "CMB0")
      (value "MA01-1")
      (footprint "eagle-import:MA01-1")
      (libsource (lib "eagle-import") (part "MA01-1"))
    )
    (comp (ref "CMB1")
      (value "MA01-1")
      (footprint "eagle-import:MA01-1")
      (libsource (lib "eagle-import") (part "MA01-1"))
    )
    (comp (ref "CMB2")
      (value "MA01-1")
      (footprint "eagle-import:MA01-1")
      (libsource (lib "eagle-import") (part "MA01-1"))
    )
    (comp (ref "CMB3")
      (value "MA01-1")
      (footprint "eagle-import:MA01-1")
      (libsource (lib "eagle-import") (part "MA01-1"))
    )
    (comp (ref "CMB4")
      (value "MA01-1")
      (footprint "eagle-import:MA01-1")
      (libsource (lib "eagle-import") (part "MA01-1"))
    )
    (comp (ref "CMB5")
      (value "MA01-1")
      (footprint "eagle-import:MA01-1")
      (libsource (lib "eagle-import") (part "MA01-1"))
    )
    (comp (ref "CMB6")
      (value "MA01-1")
      (footprint "eagle-import:MA01-1")
      (libsource (lib "eagle-import") (part "MA01-1"))
    )
    (comp (ref "CMB7")
      (value "MA01-1")
      (footprint "eagle-import:MA01-1")
      (libsource (lib "eagle-import") (part "MA01-1"))
    )
    (comp (ref "CPC0")
      (value "MA01-1")
      (footprint "eagle-import:MA01-1")
      (libsource (lib "eagle-import") (part "MA01-1"))
    )
    (comp (ref "CPC1")
      (value "MA01-1")
      (footprint "eagle-import:MA01-1")
      (libsource (lib "eagle-import") (part "MA01-1"))
    )
    (comp (ref "CPC2")
      (value "MA01-1")
      (footprint "eagle-import:MA01-1")
      (libsource (lib "eagle-import") (part "MA01-1"))
    )
    (comp (ref "CPC3")
      (value "MA01-1")
      (footprint "eagle-import:MA01-1")
      (libsource (lib "eagle-import") (part "MA01-1"))
    )
    (comp (ref "CPC4")
      (value "MA01-1")
      (footprint "eagle-import:MA01-1")
      (libsource (lib "eagle-import") (part "MA01-1"))
    )
    (comp (ref "CSR0")
      (value "MA01-1")
      (footprint "eagle-import:MA01-1")
      (libsource (lib "eagle-import") (part "MA01-1"))
    )
    (comp (ref "CSR1")
      (value "MA01-1")
      (footprint "eagle-import:MA01-1")
      (libsource (lib "eagle-import") (part "MA01-1"))
    )
    (comp (ref "CSR2")
      (value "MA01-1")
      (footprint "eagle-import:MA01-1")
      (libsource (lib "eagle-import") (part "MA01-1"))
    )
    (comp (ref "CSR3")
      (value "MA01-1")
      (footprint "eagle-import:MA01-1")
      (libsource (lib "eagle-import") (part "MA01-1"))
    )
    (comp (ref "CSR4")
      (value "MA01-1")
      (footprint "eagle-import:MA01-1")
      (libsource (lib "eagle-import") (part "MA01-1"))
    )
    (comp (ref "CSR5")
      (value "MA01-1")
      (footprint "eagle-import:MA01-1")
      (libsource (lib "eagle-import") (part "MA01-1"))
    )
    (comp (ref "CSR6")
      (value "MA01-1")
      (footprint "eagle-import:MA01-1")
      (libsource (lib "eagle-import") (part "MA01-1"))
    )
    (comp (ref "CSR7")
      (value "MA01-1")
      (footprint "eagle-import:MA01-1")
      (libsource (lib "eagle-import") (part "MA01-1"))
    )
    (comp (ref "DATA-ID0")
      (value "MA01-1")
      (footprint "eagle-import:MA01-1")
      (libsource (lib "eagle-import") (part "MA01-1"))
    )
    (comp (ref "DATA-ID1")
      (value "MA01-1")
      (footprint "eagle-import:MA01-1")
      (libsource (lib "eagle-import") (part "MA01-1"))
    )
    (comp (ref "DATA-OD0")
      (value "MA01-1")
      (footprint "eagle-import:MA01-1")
      (libsource (lib "eagle-import") (part "MA01-1"))
    )
    (comp (ref "DATA-OD1")
      (value "MA01-1")
      (footprint "eagle-import:MA01-1")
      (libsource (lib "eagle-import") (part "MA01-1"))
    )
    (comp (ref "E8/10T")
      (value "MCMURDO-16")
      (footprint "eagle-import:133-12-17")
      (libsource (lib "eagle-import") (part "MCMURDO-16"))
    )
    (comp (ref "E8/10T-2")
      (value "MCMURDO-16")
      (footprint "eagle-import:133-12-17")
      (libsource (lib "eagle-import") (part "MCMURDO-16"))
    )
    (comp (ref "E8/A")
      (value "MCMURDO-16")
      (footprint "eagle-import:133-12-17")
      (libsource (lib "eagle-import") (part "MCMURDO-16"))
    )
    (comp (ref "E8/A-2")
      (value "MCMURDO-16")
      (footprint "eagle-import:133-12-17")
      (libsource (lib "eagle-import") (part "MCMURDO-16"))
    )
    (comp (ref "E8/D")
      (value "MCMURDO-32")
      (footprint "eagle-import:133-14-17")
      (libsource (lib "eagle-import") (part "MCMURDO-32"))
    )
    (comp (ref "E8/D-2")
      (value "MCMURDO-16")
      (footprint "eagle-import:133-12-17")
      (libsource (lib "eagle-import") (part "MCMURDO-16"))
    )
    (comp (ref "E8/M")
      (value "MCMURDO-32")
      (footprint "eagle-import:133-14-17")
      (libsource (lib "eagle-import") (part "MCMURDO-32"))
    )
    (comp (ref "E8/M-2")
      (value "MCMURDO-16")
      (footprint "eagle-import:133-12-17")
      (libsource (lib "eagle-import") (part "MCMURDO-16"))
    )
    (comp (ref "E8/P")
      (value "MCMURDO-32")
      (footprint "eagle-import:133-14-17")
      (libsource (lib "eagle-import") (part "MCMURDO-32"))
    )
    (comp (ref "E8/P-2")
      (value "MCMURDO-16")
      (footprint "eagle-import:133-12-17")
      (libsource (lib "eagle-import") (part "MCMURDO-16"))
    )
    (comp (ref "E8/T")
      (value "MCMURDO-32")
      (footprint "eagle-import:133-14-17")
      (libsource (lib "eagle-import") (part "MCMURDO-32"))
    )
    (comp (ref "R63")
      (value "680")
      (footprint "eagle-import:0207_15")
      (libsource (lib "eagle-import") (part "R-US_0207/15"))
    )
    (comp (ref "R64")
      (value "680")
      (footprint "eagle-import:0207_15")
      (libsource (lib "eagle-import") (part "R-US_0207/15"))
    )
    (comp (ref "R65")
      (value "4700")
      (footprint "eagle-import:0207_15")
      (libsource (lib "eagle-import") (part "R-US_0207/15"))
    )
    (comp (ref "R66")
      (value "4700")
      (footprint "eagle-import:0207_15")
      (libsource (lib "eagle-import") (part "R-US_0207/15"))
    )
  )
  (nets
    (net (code "1") (name "+5V") (class "Default")
      (node (ref "+5V") (pin "1") (pinfunction "1_1") (pintype "passive"))
      (node (ref "C10") (pin "1") (pinfunction "1_1") (pintype "passive"))
      (node (ref "C8") (pin "1") (pinfunction "1_1") (pintype "passive"))
      (node (ref "C9") (pin "1") (pinfunction "1_1") (pintype "passive"))
      (node (ref "E8/10T") (pin "2") (pinfunction "2_2") (pintype "passive"))
      (node (ref "E8/10T") (pin "3") (pinfunction "3_3") (pintype "passive"))
      (node (ref "E8/A") (pin "2") (pinfunction "2_2") (pintype "passive"))
      (node (ref "E8/A") (pin "3") (pinfunction "3_3") (pintype "passive"))
      (node (ref "E8/D") (pin "2") (pinfunction "2_2") (pintype "passive"))
      (node (ref "E8/M") (pin "2") (pinfunction "2_2") (pintype "passive"))
      (node (ref "E8/M") (pin "3") (pinfunction "3_3") (pintype "passive"))
      (node (ref "E8/P") (pin "2") (pinfunction "2_2") (pintype "passive"))
      (node (ref "E8/P") (pin "3") (pinfunction "3_3") (pintype "passive"))
      (node (ref "E8/T") (pin "2") (pinfunction "2_2") (pintype "passive"))
      (node (ref "R63") (pin "2") (pinfunction "2_2") (pintype "passive"))
      (node (ref "R64") (pin "2") (pinfunction "2_2") (pintype "passive"))
      (node (ref "R65") (pin "2") (pinfunction "2_2") (pintype "passive"))
      (node (ref "R66") (pin "2") (pinfunction "2_2") (pintype "passive"))
    )
    (net (code "2") (name "AC0") (class "Default")
      (node (ref "AC") (pin "1") (pinfunction "1_1") (pintype "passive"))
      (node (ref "IC3") (pin "5") (pinfunction "I_5") (pintype "input"))
    )
    (net (code "3") (name "AC1") (class "Default")
      (node (ref "AC") (pin "2") (pinfunction "2_2") (pintype "passive"))
      (node (ref "IC3") (pin "3") (pinfunction "I_3") (pintype "input"))
    )
    (net (code "4") (name "AC2") (class "Default")
      (node (ref "AC") (pin "3") (pinfunction "3_3") (pintype "passive"))
      (node (ref "IC3") (pin "1") (pinfunction "I_1") (pintype "input"))
    )
    (net (code "5") (name "AC3") (class "Default")
      (node (ref "AC") (pin "4") (pinfunction "4_4") (pintype "passive"))
      (node (ref "IC3") (pin "9") (pinfunction "I_9") (pintype "input"))
    )
    (net (code "6") (name "AC4") (class "Default")
      (node (ref "AC") (pin "5") (pinfunction "5_5") (pintype "passive"))
      (node (ref "IC3") (pin "11") (pinfunction "I_11") (pintype "input"))
    )
    (net (code "7") (name "AC5") (class "Default")
      (node (ref "AC") (pin "6") (pinfunction "6_6") (pintype "passive"))
      (node (ref "IC3") (pin "13") (pinfunction "I_13") (pintype "input"))
    )
    (net (code "8") (name "AC6") (class "Default")
      (node (ref "AC") (pin "7") (pinfunction "7_7") (pintype "passive"))
      (node (ref "IC1") (pin "1") (pinfunction "I_1") (pintype "input"))
    )
    (net (code "9") (name "AC7") (class "Default")
      (node (ref "AC") (pin "8") (pinfunction "8_8") (pintype "passive"))
      (node (ref "IC1") (pin "3") (pinfunction "I_3") (pintype "input"))
    )
    (net (code "10") (name "AND") (class "Default")
      (node (ref "AND") (pin "1") (pinfunction "1_1") (pintype "passive"))
      (node (ref "IC11") (pin "3") (pinfunction "I_3") (pintype "input"))
    )
    (net (code "11") (name "CAC0") (class "Default")
      (node (ref "CAC0") (pin "1") (pinfunction "1_1") (pintype "passive"))
      (node (ref "E8/A-2") (pin "9") (pinfunction "9_9") (pintype "passive"))
    )
    (net (code "12") (name "CAC1") (class "Default")
      (node (ref "CAC1") (pin "1") (pinfunction "1_1") (pintype "passive"))
      (node (ref "E8/A-2") (pin "10") (pinfunction "10_10") (pintype "passive"))
    )
    (net (code "13") (name "CAC2") (class "Default")
      (node (ref "CAC2") (pin "1") (pinfunction "1_1") (pintype "passive"))
      (node (ref "E8/A-2") (pin "11") (pinfunction "11_11") (pintype "passive"))
    )
    (net (code "14") (name "CAC3") (class "Default")
      (node (ref "CAC3") (pin "1") (pinfunction "1_1") (pintype "passive"))
      (node (ref "E8/A-2") (pin "12") (pinfunction "12_12") (pintype "passive"))
    )
    (net (code "15") (name "CAC4") (class "Default")
      (node (ref "CAC4") (pin "1") (pinfunction "1_1") (pintype "passive"))
      (node (ref "E8/A-2") (pin "13") (pinfunction "13_13") (pintype "passive"))
    )
    (net (code "16") (name "CAC5") (class "Default")
      (node (ref "CAC5") (pin "1") (pinfunction "1_1") (pintype "passive"))
      (node (ref "E8/A-2") (pin "14") (pinfunction "14_14") (pintype "passive"))
    )
    (net (code "17") (name "CAC6") (class "Default")
      (node (ref "CAC6") (pin "1") (pinfunction "1_1") (pintype "passive"))
      (node (ref "E8/A-2") (pin "15") (pinfunction "15_15") (pintype "passive"))
    )
    (net (code "18") (name "CAC7") (class "Default")
      (node (ref "CAC7") (pin "1") (pinfunction "1_1") (pintype "passive"))
      (node (ref "E8/A-2") (pin "16") (pinfunction "16_16") (pintype "passive"))
      (node (ref "E8/P-2") (pin "8") (pinfunction "8_8") (pintype "passive"))
    )
    (net (code "19") (name "CCLOCK_RATE") (class "Default")
      (node (ref "CCLOCK_RATE") (pin "1") (pinfunction "1_1") (pintype "passive"))
      (node (ref "E8/T") (pin "7") (pinfunction "7_7") (pintype "passive"))
    )
    (net (code "20") (name "CHLT_COMM") (class "Default")
      (node (ref "CHLT_COMM") (pin "1") (pinfunction "1_1") (pintype "passive"))
      (node (ref "E8/T") (pin "5") (pinfunction "5_5") (pintype "passive"))
    )
    (net (code "21") (name "CLA2") (class "Default")
      (node (ref "CLA2") (pin "1") (pinfunction "1_1") (pintype "passive"))
    )
    (net (code "22") (name "CLOCK_RATE") (class "Default")
      (node (ref "C4") (pin "+") (pinfunction "+_+") (pintype "passive"))
      (node (ref "CLOCK_RATE") (pin "1") (pinfunction "1_1") (pintype "passive"))
    )
    (net (code "23") (name "CMA0") (class "Default")
      (node (ref "CMA0") (pin "1") (pinfunction "1_1") (pintype "passive"))
      (node (ref "E8/M-2") (pin "4") (pinfunction "4_4") (pintype "passive"))
    )
    (net (code "24") (name "CMA1") (class "Default")
      (node (ref "CMA1") (pin "1") (pinfunction "1_1") (pintype "passive"))
      (node (ref "E8/M-2") (pin "5") (pinfunction "5_5") (pintype "passive"))
    )
    (net (code "25") (name "CMA2") (class "Default")
      (node (ref "CMA2") (pin "1") (pinfunction "1_1") (pintype "passive"))
      (node (ref "E8/M-2") (pin "6") (pinfunction "6_6") (pintype "passive"))
    )
    (net (code "26") (name "CMA3") (class "Default")
      (node (ref "CMA3") (pin "1") (pinfunction "1_1") (pintype "passive"))
      (node (ref "E8/M-2") (pin "7") (pinfunction "7_7") (pintype "passive"))
    )
    (net (code "27") (name "CMA4") (class "Default")
      (node (ref "CMA4") (pin "1") (pinfunction "1_1") (pintype "passive"))
      (node (ref "E8/M-2") (pin "8") (pinfunction "8_8") (pintype "passive"))
    )
    (net (code "28") (name "CMB0") (class "Default")
      (node (ref "CMB0") (pin "1") (pinfunction "1_1") (pintype "passive"))
      (node (ref "E8/D-2") (pin "9") (pinfunction "9_9") (pintype "passive"))
      (node (ref "E8/M-2") (pin "9") (pinfunction "9_9") (pintype "passive"))
    )
    (net (code "29") (name "CMB1") (class "Default")
      (node (ref "CMB1") (pin "1") (pinfunction "1_1") (pintype "passive"))
      (node (ref "E8/D-2") (pin "10") (pinfunction "10_10") (pintype "passive"))
      (node (ref "E8/M-2") (pin "10") (pinfunction "10_10") (pintype "passive"))
    )
    (net (code "30") (name "CMB2") (class "Default")
      (node (ref "CMB2") (pin "1") (pinfunction "1_1") (pintype "passive"))
      (node (ref "E8/D-2") (pin "11") (pinfunction "11_11") (pintype "passive"))
      (node (ref "E8/M-2") (pin "11") (pinfunction "11_11") (pintype "passive"))
    )
    (net (code "31") (name "CMB3") (class "Default")
      (node (ref "CMB3") (pin "1") (pinfunction "1_1") (pintype "passive"))
      (node (ref "E8/D-2") (pin "12") (pinfunction "12_12") (pintype "passive"))
      (node (ref "E8/M-2") (pin "12") (pinfunction "12_12") (pintype "passive"))
    )
    (net (code "32") (name "CMB4") (class "Default")
      (node (ref "CMB4") (pin "1") (pinfunction "1_1") (pintype "passive"))
      (node (ref "E8/D-2") (pin "13") (pinfunction "13_13") (pintype "passive"))
      (node (ref "E8/M-2") (pin "13") (pinfunction "13_13") (pintype "passive"))
    )
    (net (code "33") (name "CMB5") (class "Default")
      (node (ref "CMB5") (pin "1") (pinfunction "1_1") (pintype "passive"))
      (node (ref "E8/D-2") (pin "14") (pinfunction "14_14") (pintype "passive"))
      (node (ref "E8/M-2") (pin "14") (pinfunction "14_14") (pintype "passive"))
    )
    (net (code "34") (name "CMB6") (class "Default")
      (node (ref "CMB6") (pin "1") (pinfunction "1_1") (pintype "passive"))
      (node (ref "E8/D-2") (pin "15") (pinfunction "15_15") (pintype "passive"))
      (node (ref "E8/M-2") (pin "15") (pinfunction "15_15") (pintype "passive"))
    )
    (net (code "35") (name "CMB7") (class "Default")
      (node (ref "CMB7") (pin "1") (pinfunction "1_1") (pintype "passive"))
      (node (ref "E8/D-2") (pin "16") (pinfunction "16_16") (pintype "passive"))
      (node (ref "E8/M-2") (pin "16") (pinfunction "16_16") (pintype "passive"))
    )
    (net (code "36") (name "CPC0") (class "Default")
      (node (ref "CPC0") (pin "1") (pinfunction "1_1") (pintype "passive"))
      (node (ref "E8/P-2") (pin "9") (pinfunction "9_9") (pintype "passive"))
    )
    (net (code "37") (name "CPC1") (class "Default")
      (node (ref "CPC1") (pin "1") (pinfunction "1_1") (pintype "passive"))
      (node (ref "E8/P-2") (pin "10") (pinfunction "10_10") (pintype "passive"))
    )
    (net (code "38") (name "CPC2") (class "Default")
      (node (ref "CPC2") (pin "1") (pinfunction "1_1") (pintype "passive"))
      (node (ref "E8/P-2") (pin "11") (pinfunction "11_11") (pintype "passive"))
    )
    (net (code "39") (name "CPC3") (class "Default")
      (node (ref "CPC3") (pin "1") (pinfunction "1_1") (pintype "passive"))
      (node (ref "E8/P-2") (pin "12") (pinfunction "12_12") (pintype "passive"))
    )
    (net (code "40") (name "CPC4") (class "Default")
      (node (ref "CPC4") (pin "1") (pinfunction "1_1") (pintype "passive"))
      (node (ref "E8/P-2") (pin "13") (pinfunction "13_13") (pintype "passive"))
    )
    (net (code "41") (name "CSR0") (class "Default")
      (node (ref "CSR0") (pin "1") (pinfunction "1_1") (pintype "passive"))
      (node (ref "E8/M") (pin "24") (pinfunction "24_24") (pintype "passive"))
      (node (ref "E8/P") (pin "24") (pinfunction "24_24") (pintype "passive"))
    )
    (net (code "42") (name "CSR1") (class "Default")
      (node (ref "CSR1") (pin "1") (pinfunction "1_1") (pintype "passive"))
      (node (ref "E8/M") (pin "25") (pinfunction "25_25") (pintype "passive"))
      (node (ref "E8/P") (pin "25") (pinfunction "25_25") (pintype "passive"))
    )
    (net (code "43") (name "CSR2") (class "Default")
      (node (ref "CSR2") (pin "1") (pinfunction "1_1") (pintype "passive"))
      (node (ref "E8/M") (pin "26") (pinfunction "26_26") (pintype "passive"))
      (node (ref "E8/P") (pin "26") (pinfunction "26_26") (pintype "passive"))
    )
    (net (code "44") (name "CSR3") (class "Default")
      (node (ref "CSR3") (pin "1") (pinfunction "1_1") (pintype "passive"))
      (node (ref "E8/M") (pin "27") (pinfunction "27_27") (pintype "passive"))
      (node (ref "E8/P") (pin "27") (pinfunction "27_27") (pintype "passive"))
    )
    (net (code "45") (name "CSR4") (class "Default")
      (node (ref "CSR4") (pin "1") (pinfunction "1_1") (pintype "passive"))
      (node (ref "E8/M") (pin "28") (pinfunction "28_28") (pintype "passive"))
      (node (ref "E8/P") (pin "28") (pinfunction "28_28") (pintype "passive"))
    )
    (net (code "46") (name "CSR5") (class "Default")
      (node (ref "CSR5") (pin "1") (pinfunction "1_1") (pintype "passive"))
      (node (ref "E8/M") (pin "29") (pinfunction "29_29") (pintype "passive"))
    )
    (net (code "47") (name "CSR6") (class "Default")
      (node (ref "CSR6") (pin "1") (pinfunction "1_1") (pintype "passive"))
      (node (ref "E8/M") (pin "30") (pinfunction "30_30") (pintype "passive"))
    )
    (net (code "48") (name "CSR7") (class "Default")
      (node (ref "CSR7") (pin "1") (pinfunction "1_1") (pintype "passive"))
      (node (ref "E8/M") (pin "31") (pinfunction "31_31") (pintype "passive"))
    )
    (net (code "49") (name "DATA-ID0") (class "Default")
      (node (ref "DATA-ID0") (pin "1") (pinfunction "1_1") (pintype "passive"))
      (node (ref "E8/10T-2") (pin "13") (pinfunction "13_13") (pintype "passive"))
    )
    (net (code "50") (name "DATA-ID1") (class "Default")
      (node (ref "DATA-ID1") (pin "1") (pinfunction "1_1") (pintype "passive"))
      (node (ref "E8/10T-2") (pin "9") (pinfunction "9_9") (pintype "passive"))
    )
    (net (code "51") (name "DATA-OD0") (class "Default")
      (node (ref "DATA-OD0") (pin "1") (pinfunction "1_1") (pintype "passive"))
      (node (ref "E8/10T-2") (pin "5") (pinfunction "5_5") (pintype "passive"))
    )
    (net (code "52") (name "DATA-OD1") (class "Default")
      (node (ref "DATA-OD1") (pin "1") (pinfunction "1_1") (pintype "passive"))
      (node (ref "E8/10T-2") (pin "1") (pinfunction "1_1") (pintype "passive"))
    )
    (net (code "53") (name "DCA") (class "Default")
      (node (ref "DCA") (pin "1") (pinfunction "1_1") (pintype "passive"))
      (node (ref "IC10") (pin "11") (pinfunction "I_11") (pintype "input"))
    )
    (net (code "54") (name "GND") (class "Default")
      (node (ref "C3") (pin "2") (pinfunction "2_2") (pintype "passive"))
      (node (ref "C5") (pin "2") (pinfunction "2_2") (pintype "passive"))
      (node (ref "C6") (pin "2") (pinfunction "2_2") (pintype "passive"))
      (node (ref "C7") (pin "2") (pinfunction "2_2") (pintype "passive"))
      (node (ref "DEP") (pin "2") (pinfunction "P_2") (pintype "passive"))
      (node (ref "EXAM") (pin "2") (pinfunction "P_2") (pintype "passive"))
      (node (ref "GND") (pin "1") (pinfunction "1_1") (pintype "passive"))
      (node (ref "HALT") (pin "3") (pinfunction "S_3") (pintype "passive"))
      (node (ref "IC12") (pin "4") (pinfunction "B_4") (pintype "input"))
      (node (ref "LA") (pin "2") (pinfunction "P_2") (pintype "passive"))
      (node (ref "LA") (pin "3") (pinfunction "S_3") (pintype "passive"))
      (node (ref "RUN") (pin "2") (pinfunction "P_2") (pintype "passive"))
      (node (ref "SLOW") (pin "3") (pinfunction "S_3") (pintype "passive"))
      (node (ref "STEP") (pin "2") (pinfunction "P_2") (pintype "passive"))
      (node (ref "STEP") (pin "3") (pinfunction "S_3") (pintype "passive"))
      (node (ref "SW0") (pin "3") (pinfunction "S_3") (pintype "passive"))
      (node (ref "SW1") (pin "3") (pinfunction "S_3") (pintype "passive"))
      (node (ref "SW2") (pin "3") (pinfunction "S_3") (pintype "passive"))
      (node (ref "SW3") (pin "3") (pinfunction "S_3") (pintype "passive"))
      (node (ref "SW4") (pin "3") (pinfunction "S_3") (pintype "passive"))
      (node (ref "SW5") (pin "3") (pinfunction "S_3") (pintype "passive"))
      (node (ref "SW6") (pin "3") (pinfunction "S_3") (pintype "passive"))
      (node (ref "SW7") (pin "3") (pinfunction "S_3") (pintype "passive"))
    )
    (net (code "55") (name "GND2") (class "Default")
      (node (ref "C10") (pin "2") (pinfunction "2_2") (pintype "passive"))
      (node (ref "C8") (pin "2") (pinfunction "2_2") (pintype "passive"))
      (node (ref "C9") (pin "2") (pinfunction "2_2") (pintype "passive"))
      (node (ref "CGND") (pin "1") (pinfunction "1_1") (pintype "passive"))
      (node (ref "E8/10T") (pin "1") (pinfunction "1_1") (pintype "passive"))
      (node (ref "E8/10T") (pin "16") (pinfunction "16_16") (pintype "passive"))
      (node (ref "E8/A") (pin "1") (pinfunction "1_1") (pintype "passive"))
      (node (ref "E8/A") (pin "16") (pinfunction "16_16") (pintype "passive"))
      (node (ref "E8/D") (pin "1") (pinfunction "1_1") (pintype "passive"))
      (node (ref "E8/D") (pin "32") (pinfunction "32_32") (pintype "passive"))
      (node (ref "E8/M") (pin "1") (pinfunction "1_1") (pintype "passive"))
      (node (ref "E8/M") (pin "32") (pinfunction "32_32") (pintype "passive"))
      (node (ref "E8/P") (pin "1") (pinfunction "1_1") (pintype "passive"))
      (node (ref "E8/P") (pin "32") (pinfunction "32_32") (pintype "passive"))
      (node (ref "E8/T") (pin "1") (pinfunction "1_1") (pintype "passive"))
      (node (ref "E8/T") (pin "32") (pinfunction "32_32") (pintype "passive"))
    )
    (net (code "56") (name "HLT_COMM") (class "Default")
      (node (ref "HLT_COMM") (pin "1") (pinfunction "1_1") (pintype "passive"))
      (node (ref "IC9") (pin "6") (pinfunction "O_6") (pintype "output"))
    )
    (net (code "57") (name "IOT") (class "Default")
      (node (ref "IC10") (pin "3") (pinfunction "I_3") (pintype "input"))
      (node (ref "IOT") (pin "1") (pinfunction "1_1") (pintype "passive"))
    )
    (net (code "58") (name "ISZ") (class "Default")
      (node (ref "IC10") (pin "9") (pinfunction "I_9") (pintype "input"))
      (node (ref "ISZ") (pin "1") (pinfunction "1_1") (pintype "passive"))
    )
    (net (code "59") (name "JMP") (class "Default")
      (node (ref "IC10") (pin "5") (pinfunction "I_5") (pintype "input"))
      (node (ref "JMP") (pin "1") (pinfunction "1_1") (pintype "passive"))
    )
    (net (code "60") (name "JMS") (class "Default")
      (node (ref "IC10") (pin "13") (pinfunction "I_13") (pintype "input"))
      (node (ref "JMS") (pin "1") (pinfunction "1_1") (pintype "passive"))
    )
    (net (code "61") (name "LA2") (class "Default")
      (node (ref "IC9") (pin "8") (pinfunction "O_8") (pintype "output"))
      (node (ref "LA2") (pin "1") (pinfunction "1_1") (pintype "passive"))
    )
    (net (code "62") (name "MA0") (class "Default")
      (node (ref "IC5") (pin "13") (pinfunction "I_13") (pintype "input"))
      (node (ref "MA0") (pin "1") (pinfunction "1_1") (pintype "passive"))
    )
    (net (code "63") (name "MA1") (class "Default")
      (node (ref "IC5") (pin "9") (pinfunction "I_9") (pintype "input"))
      (node (ref "MA1") (pin "1") (pinfunction "1_1") (pintype "passive"))
    )
    (net (code "64") (name "MA2") (class "Default")
      (node (ref "IC5") (pin "3") (pinfunction "I_3") (pintype "input"))
      (node (ref "MA2") (pin "1") (pinfunction "1_1") (pintype "passive"))
    )
    (net (code "65") (name "MA3") (class "Default")
      (node (ref "IC4") (pin "13") (pinfunction "I_13") (pintype "input"))
      (node (ref "MA3") (pin "1") (pinfunction "1_1") (pintype "passive"))
    )
    (net (code "66") (name "MA4") (class "Default")
      (node (ref "IC4") (pin "9") (pinfunction "I_9") (pintype "input"))
      (node (ref "MA4") (pin "1") (pinfunction "1_1") (pintype "passive"))
    )
    (net (code "67") (name "MA5") (class "Default")
      (node (ref "IC4") (pin "1") (pinfunction "I_1") (pintype "input"))
      (node (ref "MA5") (pin "1") (pinfunction "1_1") (pintype "passive"))
    )
    (net (code "68") (name "MA6") (class "Default")
      (node (ref "IC4") (pin "3") (pinfunction "I_3") (pintype "input"))
      (node (ref "MA6") (pin "1") (pinfunction "1_1") (pintype "passive"))
    )
    (net (code "69") (name "MB0") (class "Default")
      (node (ref "IC2") (pin "9") (pinfunction "I_9") (pintype "input"))
      (node (ref "MB") (pin "1") (pinfunction "1_1") (pintype "passive"))
    )
    (net (code "70") (name "MB1") (class "Default")
      (node (ref "IC2") (pin "5") (pinfunction "I_5") (pintype "input"))
      (node (ref "MB") (pin "2") (pinfunction "2_2") (pintype "passive"))
    )
    (net (code "71") (name "MB2") (class "Default")
      (node (ref "IC2") (pin "3") (pinfunction "I_3") (pintype "input"))
      (node (ref "MB") (pin "3") (pinfunction "3_3") (pintype "passive"))
    )
    (net (code "72") (name "MB3") (class "Default")
      (node (ref "IC2") (pin "1") (pinfunction "I_1") (pintype "input"))
      (node (ref "MB") (pin "4") (pinfunction "4_4") (pintype "passive"))
    )
    (net (code "73") (name "MB4") (class "Default")
      (node (ref "IC1") (pin "13") (pinfunction "I_13") (pintype "input"))
      (node (ref "MB") (pin "5") (pinfunction "5_5") (pintype "passive"))
    )
    (net (code "74") (name "MB5") (class "Default")
      (node (ref "IC1") (pin "11") (pinfunction "I_11") (pintype "input"))
      (node (ref "MB") (pin "6") (pinfunction "6_6") (pintype "passive"))
    )
    (net (code "75") (name "MB6") (class "Default")
      (node (ref "IC1") (pin "9") (pinfunction "I_9") (pintype "input"))
      (node (ref "MB") (pin "7") (pinfunction "7_7") (pintype "passive"))
    )
    (net (code "76") (name "MB7") (class "Default")
      (node (ref "IC1") (pin "5") (pinfunction "I_5") (pintype "input"))
      (node (ref "MB") (pin "8") (pinfunction "8_8") (pintype "passive"))
    )
    (net (code "77") (name "N$71") (class "Default")
      (node (ref "E8/D") (pin "31") (pinfunction "31_31") (pintype "passive"))
    )
    (net (code "78") (name "N$72") (class "Default")
      (node (ref "E8/D") (pin "30") (pinfunction "30_30") (pintype "passive"))
    )
    (net (code "79") (name "N$73") (class "Default")
      (node (ref "E8/D") (pin "29") (pinfunction "29_29") (pintype "passive"))
    )
    (net (code "80") (name "N$74") (class "Default")
      (node (ref "E8/D") (pin "28") (pinfunction "28_28") (pintype "passive"))
    )
    (net (code "81") (name "N$80") (class "Default")
      (node (ref "E8/D") (pin "27") (pinfunction "27_27") (pintype "passive"))
    )
    (net (code "82") (name "N$81") (class "Default")
      (node (ref "E8/D") (pin "26") (pinfunction "26_26") (pintype "passive"))
    )
    (net (code "83") (name "N$82") (class "Default")
      (node (ref "E8/D") (pin "25") (pinfunction "25_25") (pintype "passive"))
    )
    (net (code "84") (name "N$83") (class "Default")
      (node (ref "E8/D") (pin "23") (pinfunction "23_23") (pintype "passive"))
    )
    (net (code "85") (name "N$84") (class "Default")
      (node (ref "E8/D") (pin "22") (pinfunction "22_22") (pintype "passive"))
    )
    (net (code "86") (name "N$85") (class "Default")
      (node (ref "E8/10T") (pin "15") (pinfunction "15_15") (pintype "passive"))
      (node (ref "E8/A") (pin "13") (pinfunction "13_13") (pintype "passive"))
      (node (ref "E8/M") (pin "12") (pinfunction "12_12") (pintype "passive"))
      (node (ref "E8/P") (pin "14") (pinfunction "14_14") (pintype "passive"))
      (node (ref "E8/T") (pin "16") (pinfunction "16_16") (pintype "passive"))
    )
    (net (code "87") (name "N$87") (class "Default")
      (node (ref "E8/D") (pin "21") (pinfunction "21_21") (pintype "passive"))
    )
    (net (code "88") (name "N$88") (class "Default")
      (node (ref "E8/D") (pin "20") (pinfunction "20_20") (pintype "passive"))
    )
    (net (code "89") (name "N$91") (class "Default")
      (node (ref "E8/D") (pin "19") (pinfunction "19_19") (pintype "passive"))
    )
    (net (code "90") (name "N$92") (class "Default")
      (node (ref "E8/D") (pin "18") (pinfunction "18_18") (pintype "passive"))
    )
    (net (code "91") (name "N$94") (class "Default")
      (node (ref "E8/D") (pin "17") (pinfunction "17_17") (pintype "passive"))
    )
    (net (code "92") (name "N$95") (class "Default")
      (node (ref "E8/T") (pin "31") (pinfunction "31_31") (pintype "passive"))
    )
    (net (code "93") (name "N$96") (class "Default")
      (node (ref "E8/T") (pin "30") (pinfunction "30_30") (pintype "passive"))
    )
    (net (code "94") (name "N$99") (class "Default")
      (node (ref "E8/T") (pin "29") (pinfunction "29_29") (pintype "passive"))
    )
    (net (code "95") (name "N$101") (class "Default")
      (node (ref "E8/T") (pin "28") (pinfunction "28_28") (pintype "passive"))
    )
    (net (code "96") (name "N$102") (class "Default")
      (node (ref "E8/T") (pin "27") (pinfunction "27_27") (pintype "passive"))
    )
    (net (code "97") (name "N$106") (class "Default")
      (node (ref "E8/D") (pin "8") (pinfunction "8_8") (pintype "passive"))
      (node (ref "E8/M") (pin "7") (pinfunction "7_7") (pintype "passive"))
      (node (ref "E8/T") (pin "8") (pinfunction "8_8") (pintype "passive"))
    )
    (net (code "98") (name "N$107") (class "Default")
      (node (ref "E8/T") (pin "9") (pinfunction "9_9") (pintype "passive"))
    )
    (net (code "99") (name "N$108") (class "Default")
      (node (ref "E8/T") (pin "10") (pinfunction "10_10") (pintype "passive"))
    )
    (net (code "100") (name "N$114") (class "Default")
      (node (ref "E8/T") (pin "11") (pinfunction "11_11") (pintype "passive"))
    )
    (net (code "101") (name "N$121") (class "Default")
      (node (ref "E8/T") (pin "12") (pinfunction "12_12") (pintype "passive"))
    )
    (net (code "102") (name "N$122") (class "Default")
      (node (ref "E8/T") (pin "13") (pinfunction "13_13") (pintype "passive"))
    )
    (net (code "103") (name "N$123") (class "Default")
      (node (ref "E8/T") (pin "14") (pinfunction "14_14") (pintype "passive"))
    )
    (net (code "104") (name "N$124") (class "Default")
      (node (ref "E8/T") (pin "15") (pinfunction "15_15") (pintype "passive"))
    )
    (net (code "105") (name "N$125") (class "Default")
      (node (ref "E8/T") (pin "26") (pinfunction "26_26") (pintype "passive"))
    )
    (net (code "106") (name "N$126") (class "Default")
      (node (ref "E8/T") (pin "25") (pinfunction "25_25") (pintype "passive"))
    )
    (net (code "107") (name "N$133") (class "Default")
      (node (ref "E8/T") (pin "24") (pinfunction "24_24") (pintype "passive"))
    )
    (net (code "108") (name "N$142") (class "Default")
      (node (ref "E8/T") (pin "23") (pinfunction "23_23") (pintype "passive"))
    )
    (net (code "109") (name "N$143") (class "Default")
      (node (ref "E8/T") (pin "22") (pinfunction "22_22") (pintype "passive"))
    )
    (net (code "110") (name "N$144") (class "Default")
      (node (ref "E8/T") (pin "21") (pinfunction "21_21") (pintype "passive"))
    )
    (net (code "111") (name "N$145") (class "Default")
      (node (ref "E8/T") (pin "20") (pinfunction "20_20") (pintype "passive"))
    )
    (net (code "112") (name "N$146") (class "Default")
      (node (ref "E8/T") (pin "19") (pinfunction "19_19") (pintype "passive"))
    )
    (net (code "113") (name "N$147") (class "Default")
      (node (ref "E8/T") (pin "18") (pinfunction "18_18") (pintype "passive"))
    )
    (net (code "114") (name "N$148") (class "Default")
      (node (ref "E8/T") (pin "17") (pinfunction "17_17") (pintype "passive"))
    )
    (net (code "115") (name "N$149") (class "Default")
      (node (ref "E8/D") (pin "16") (pinfunction "16_16") (pintype "passive"))
    )
    (net (code "116") (name "N$150") (class "Default")
      (node (ref "E8/D") (pin "15") (pinfunction "15_15") (pintype "passive"))
    )
    (net (code "117") (name "N$151") (class "Default")
      (node (ref "E8/D") (pin "14") (pinfunction "14_14") (pintype "passive"))
    )
    (net (code "118") (name "N$153") (class "Default")
      (node (ref "E8/D") (pin "12") (pinfunction "12_12") (pintype "passive"))
    )
    (net (code "119") (name "N$154") (class "Default")
      (node (ref "E8/D") (pin "11") (pinfunction "11_11") (pintype "passive"))
    )
    (net (code "120") (name "N$155") (class "Default")
      (node (ref "E8/D") (pin "10") (pinfunction "10_10") (pintype "passive"))
    )
    (net (code "121") (name "N$156") (class "Default")
      (node (ref "E8/D") (pin "9") (pinfunction "9_9") (pintype "passive"))
    )
    (net (code "122") (name "N$157") (class "Default")
      (node (ref "E8/M") (pin "13") (pinfunction "13_13") (pintype "passive"))
    )
    (net (code "123") (name "N$158") (class "Default")
      (node (ref "E8/D") (pin "7") (pinfunction "7_7") (pintype "passive"))
    )
    (net (code "124") (name "N$159") (class "Default")
      (node (ref "E8/D") (pin "6") (pinfunction "6_6") (pintype "passive"))
    )
    (net (code "125") (name "N$160") (class "Default")
      (node (ref "E8/D") (pin "5") (pinfunction "5_5") (pintype "passive"))
    )
    (net (code "126") (name "N$161") (class "Default")
      (node (ref "E8/M") (pin "6") (pinfunction "6_6") (pintype "passive"))
    )
    (net (code "127") (name "N$162") (class "Default")
      (node (ref "E8/D") (pin "13") (pinfunction "13_13") (pintype "passive"))
    )
    (net (code "128") (name "N$171") (class "Default")
      (node (ref "E8/M") (pin "22") (pinfunction "22_22") (pintype "passive"))
    )
    (net (code "129") (name "N$172") (class "Default")
      (node (ref "E8/M") (pin "21") (pinfunction "21_21") (pintype "passive"))
    )
    (net (code "130") (name "N$173") (class "Default")
      (node (ref "E8/M") (pin "20") (pinfunction "20_20") (pintype "passive"))
    )
    (net (code "131") (name "N$174") (class "Default")
      (node (ref "E8/M") (pin "19") (pinfunction "19_19") (pintype "passive"))
    )
    (net (code "132") (name "N$175") (class "Default")
      (node (ref "E8/M") (pin "18") (pinfunction "18_18") (pintype "passive"))
    )
    (net (code "133") (name "N$176") (class "Default")
      (node (ref "E8/M") (pin "17") (pinfunction "17_17") (pintype "passive"))
    )
    (net (code "134") (name "N$177") (class "Default")
      (node (ref "E8/M") (pin "16") (pinfunction "16_16") (pintype "passive"))
    )
    (net (code "135") (name "N$178") (class "Default")
      (node (ref "E8/M") (pin "15") (pinfunction "15_15") (pintype "passive"))
    )
    (net (code "136") (name "N$179") (class "Default")
      (node (ref "E8/M") (pin "14") (pinfunction "14_14") (pintype "passive"))
    )
    (net (code "137") (name "N$182") (class "Default")
      (node (ref "E8/M") (pin "11") (pinfunction "11_11") (pintype "passive"))
    )
    (net (code "138") (name "N$183") (class "Default")
      (node (ref "E8/M") (pin "10") (pinfunction "10_10") (pintype "passive"))
    )
    (net (code "139") (name "N$184") (class "Default")
      (node (ref "E8/M") (pin "9") (pinfunction "9_9") (pintype "passive"))
    )
    (net (code "140") (name "N$185") (class "Default")
      (node (ref "E8/M") (pin "8") (pinfunction "8_8") (pintype "passive"))
    )
    (net (code "141") (name "N$188") (class "Default")
      (node (ref "E8/M") (pin "5") (pinfunction "5_5") (pintype "passive"))
    )
    (net (code "142") (name "N$194") (class "Default")
      (node (ref "E8/M") (pin "23") (pinfunction "23_23") (pintype "passive"))
    )
    (net (code "143") (name "N$195") (class "Default")
      (node (ref "E8/P") (pin "23") (pinfunction "23_23") (pintype "passive"))
    )
    (net (code "144") (name "N$196") (class "Default")
      (node (ref "E8/P") (pin "22") (pinfunction "22_22") (pintype "passive"))
    )
    (net (code "145") (name "N$197") (class "Default")
      (node (ref "E8/P") (pin "21") (pinfunction "21_21") (pintype "passive"))
    )
    (net (code "146") (name "N$198") (class "Default")
      (node (ref "E8/P") (pin "20") (pinfunction "20_20") (pintype "passive"))
    )
    (net (code "147") (name "N$199") (class "Default")
      (node (ref "E8/P") (pin "19") (pinfunction "19_19") (pintype "passive"))
    )
    (net (code "148") (name "N$200") (class "Default")
      (node (ref "E8/P") (pin "18") (pinfunction "18_18") (pintype "passive"))
    )
    (net (code "149") (name "N$201") (class "Default")
      (node (ref "E8/P") (pin "17") (pinfunction "17_17") (pintype "passive"))
    )
    (net (code "150") (name "N$202") (class "Default")
      (node (ref "E8/P") (pin "16") (pinfunction "16_16") (pintype "passive"))
    )
    (net (code "151") (name "N$203") (class "Default")
      (node (ref "E8/P") (pin "15") (pinfunction "15_15") (pintype "passive"))
    )
    (net (code "152") (name "N$205") (class "Default")
      (node (ref "E8/P") (pin "13") (pinfunction "13_13") (pintype "passive"))
    )
    (net (code "153") (name "N$206") (class "Default")
      (node (ref "E8/P") (pin "12") (pinfunction "12_12") (pintype "passive"))
    )
    (net (code "154") (name "N$207") (class "Default")
      (node (ref "E8/P") (pin "11") (pinfunction "11_11") (pintype "passive"))
    )
    (net (code "155") (name "N$208") (class "Default")
      (node (ref "E8/P") (pin "10") (pinfunction "10_10") (pintype "passive"))
    )
    (net (code "156") (name "N$209") (class "Default")
      (node (ref "E8/P") (pin "9") (pinfunction "9_9") (pintype "passive"))
    )
    (net (code "157") (name "N$210") (class "Default")
      (node (ref "E8/P") (pin "8") (pinfunction "8_8") (pintype "passive"))
    )
    (net (code "158") (name "N$211") (class "Default")
      (node (ref "E8/P") (pin "7") (pinfunction "7_7") (pintype "passive"))
    )
    (net (code "159") (name "N$212") (class "Default")
      (node (ref "E8/P") (pin "6") (pinfunction "6_6") (pintype "passive"))
    )
    (net (code "160") (name "N$216") (class "Default")
      (node (ref "E8/P") (pin "31") (pinfunction "31_31") (pintype "passive"))
    )
    (net (code "161") (name "N$217") (class "Default")
      (node (ref "E8/P") (pin "30") (pinfunction "30_30") (pintype "passive"))
    )
    (net (code "162") (name "N$223") (class "Default")
      (node (ref "E8/A") (pin "15") (pinfunction "15_15") (pintype "passive"))
    )
    (net (code "163") (name "N$224") (class "Default")
      (node (ref "E8/A") (pin "14") (pinfunction "14_14") (pintype "passive"))
    )
    (net (code "164") (name "N$226") (class "Default")
      (node (ref "E8/A") (pin "12") (pinfunction "12_12") (pintype "passive"))
    )
    (net (code "165") (name "N$227") (class "Default")
      (node (ref "E8/A") (pin "11") (pinfunction "11_11") (pintype "passive"))
    )
    (net (code "166") (name "N$228") (class "Default")
      (node (ref "E8/A") (pin "10") (pinfunction "10_10") (pintype "passive"))
    )
    (net (code "167") (name "N$229") (class "Default")
      (node (ref "E8/A") (pin "9") (pinfunction "9_9") (pintype "passive"))
    )
    (net (code "168") (name "N$230") (class "Default")
      (node (ref "E8/A") (pin "8") (pinfunction "8_8") (pintype "passive"))
    )
    (net (code "169") (name "N$231") (class "Default")
      (node (ref "E8/A") (pin "7") (pinfunction "7_7") (pintype "passive"))
    )
    (net (code "170") (name "N$232") (class "Default")
      (node (ref "E8/A") (pin "6") (pinfunction "6_6") (pintype "passive"))
    )
    (net (code "171") (name "N$240") (class "Default")
      (node (ref "E8/10T") (pin "14") (pinfunction "14_14") (pintype "passive"))
    )
    (net (code "172") (name "N$241") (class "Default")
      (node (ref "E8/10T") (pin "13") (pinfunction "13_13") (pintype "passive"))
    )
    (net (code "173") (name "N$242") (class "Default")
      (node (ref "E8/10T") (pin "12") (pinfunction "12_12") (pintype "passive"))
    )
    (net (code "174") (name "N$243") (class "Default")
      (node (ref "E8/10T") (pin "11") (pinfunction "11_11") (pintype "passive"))
    )
    (net (code "175") (name "N$244") (class "Default")
      (node (ref "E8/10T") (pin "10") (pinfunction "10_10") (pintype "passive"))
    )
    (net (code "176") (name "N$245") (class "Default")
      (node (ref "E8/10T") (pin "9") (pinfunction "9_9") (pintype "passive"))
    )
    (net (code "177") (name "N$246") (class "Default")
      (node (ref "E8/10T") (pin "8") (pinfunction "8_8") (pintype "passive"))
    )
    (net (code "178") (name "N$247") (class "Default")
      (node (ref "E8/10T") (pin "7") (pinfunction "7_7") (pintype "passive"))
    )
    (net (code "179") (name "N$248") (class "Default")
      (node (ref "E8/10T") (pin "6") (pinfunction "6_6") (pintype "passive"))
    )
    (net (code "180") (name "N$296") (class "Default")
      (node (ref "E8/A-2") (pin "5") (pinfunction "5_5") (pintype "passive"))
      (node (ref "E8/P-2") (pin "6") (pinfunction "6_6") (pintype "passive"))
    )
    (net (code "181") (name "N$297") (class "Default")
      (node (ref "E8/A-2") (pin "4") (pinfunction "4_4") (pintype "passive"))
      (node (ref "E8/P-2") (pin "5") (pinfunction "5_5") (pintype "passive"))
    )
    (net (code "182") (name "N$310") (class "Default")
      (node (ref "E8/A-2") (pin "8") (pinfunction "8_8") (pintype "passive"))
    )
    (net (code "183") (name "N$311") (class "Default")
      (node (ref "E8/A-2") (pin "7") (pinfunction "7_7") (pintype "passive"))
    )
    (net (code "184") (name "N$312") (class "Default")
      (node (ref "E8/A-2") (pin "6") (pinfunction "6_6") (pintype "passive"))
    )
    (net (code "185") (name "Net-(DEP-O)") (class "Default")
      (node (ref "DEP") (pin "1") (pinfunction "O_1") (pintype "passive"))
      (node (ref "IC6") (pin "9") (pinfunction "I0_9") (pintype "input"))
      (node (ref "R57") (pin "1") (pinfunction "1_1") (pintype "passive"))
    )
    (net (code "186") (name "Net-(DEP-S)") (class "Default")
      (node (ref "DEP") (pin "3") (pinfunction "S_3") (pintype "passive"))
      (node (ref "IC6") (pin "13") (pinfunction "I1_13") (pintype "input"))
      (node (ref "R58") (pin "1") (pinfunction "1_1") (pintype "passive"))
    )
    (net (code "187") (name "Net-(E8/10T-Pad4)") (class "Default")
      (node (ref "E8/10T") (pin "4") (pinfunction "4_4") (pintype "passive"))
      (node (ref "E8/A") (pin "4") (pinfunction "4_4") (pintype "passive"))
      (node (ref "E8/P") (pin "4") (pinfunction "4_4") (pintype "passive"))
      (node (ref "R63") (pin "1") (pinfunction "1_1") (pintype "passive"))
    )
    (net (code "188") (name "Net-(E8/10T-Pad5)") (class "Default")
      (node (ref "E8/10T") (pin "5") (pinfunction "5_5") (pintype "passive"))
      (node (ref "E8/D") (pin "4") (pinfunction "4_4") (pintype "passive"))
    )
    (net (code "189") (name "Net-(E8/A-Pad5)") (class "Default")
      (node (ref "E8/A") (pin "5") (pinfunction "5_5") (pintype "passive"))
      (node (ref "E8/M") (pin "4") (pinfunction "4_4") (pintype "passive"))
      (node (ref "E8/P") (pin "5") (pinfunction "5_5") (pintype "passive"))
      (node (ref "R64") (pin "1") (pinfunction "1_1") (pintype "passive"))
    )
    (net (code "190") (name "Net-(E8/D-Pad3)") (class "Default")
      (node (ref "E8/D") (pin "3") (pinfunction "3_3") (pintype "passive"))
      (node (ref "E8/T") (pin "3") (pinfunction "3_3") (pintype "passive"))
    )
    (net (code "191") (name "Net-(E8/M-2-Pad1)") (class "Default")
      (node (ref "E8/M-2") (pin "1") (pinfunction "1_1") (pintype "passive"))
      (node (ref "E8/P-2") (pin "1") (pinfunction "1_1") (pintype "passive"))
    )
    (net (code "192") (name "Net-(EXAM-O)") (class "Default")
      (node (ref "EXAM") (pin "1") (pinfunction "O_1") (pintype "passive"))
      (node (ref "IC6") (pin "5") (pinfunction "I1_5") (pintype "input"))
      (node (ref "R59") (pin "1") (pinfunction "1_1") (pintype "passive"))
    )
    (net (code "193") (name "Net-(EXAM-S)") (class "Default")
      (node (ref "EXAM") (pin "3") (pinfunction "S_3") (pintype "passive"))
      (node (ref "IC6") (pin "1") (pinfunction "I0_1") (pintype "input"))
      (node (ref "R60") (pin "1") (pinfunction "1_1") (pintype "passive"))
    )
    (net (code "194") (name "Net-(HALT-O)") (class "Default")
      (node (ref "HALT") (pin "1") (pinfunction "O_1") (pintype "passive"))
      (node (ref "HALT") (pin "2") (pinfunction "P_2") (pintype "passive"))
      (node (ref "IC9") (pin "4") (pinfunction "I0_4") (pintype "input"))
      (node (ref "R61") (pin "1") (pinfunction "1_1") (pintype "passive"))
      (node (ref "STEP") (pin "1") (pinfunction "O_1") (pintype "passive"))
    )
    (net (code "195") (name "Net-(IC1A-O)") (class "Default")
      (node (ref "IC1") (pin "2") (pinfunction "O_2") (pintype "open_collector"))
      (node (ref "R6") (pin "1") (pinfunction "1_1") (pintype "passive"))
    )
    (net (code "196") (name "Net-(IC1B-O)") (class "Default")
      (node (ref "IC1") (pin "4") (pinfunction "O_4") (pintype "open_collector"))
      (node (ref "LED8") (pin "K") (pinfunction "C_K") (pintype "passive"))
    )
    (net (code "197") (name "Net-(IC1C-O)") (class "Default")
      (node (ref "IC1") (pin "6") (pinfunction "O_6") (pintype "open_collector"))
      (node (ref "LED9") (pin "K") (pinfunction "C_K") (pintype "passive"))
    )
    (net (code "198") (name "Net-(IC1D-O)") (class "Default")
      (node (ref "IC1") (pin "8") (pinfunction "O_8") (pintype "open_collector"))
      (node (ref "R11") (pin "1") (pinfunction "1_1") (pintype "passive"))
    )
    (net (code "199") (name "Net-(IC1E-O)") (class "Default")
      (node (ref "IC1") (pin "10") (pinfunction "O_10") (pintype "open_collector"))
      (node (ref "R10") (pin "1") (pinfunction "1_1") (pintype "passive"))
    )
    (net (code "200") (name "Net-(IC1F-O)") (class "Default")
      (node (ref "IC1") (pin "12") (pinfunction "O_12") (pintype "open_collector"))
      (node (ref "R13") (pin "1") (pinfunction "1_1") (pintype "passive"))
    )
    (net (code "201") (name "Net-(IC2A-O)") (class "Default")
      (node (ref "IC2") (pin "2") (pinfunction "O_2") (pintype "open_collector"))
      (node (ref "R12") (pin "1") (pinfunction "1_1") (pintype "passive"))
    )
    (net (code "202") (name "Net-(IC2B-O)") (class "Default")
      (node (ref "IC2") (pin "4") (pinfunction "O_4") (pintype "open_collector"))
      (node (ref "R15") (pin "1") (pinfunction "1_1") (pintype "passive"))
    )
    (net (code "203") (name "Net-(IC2C-O)") (class "Default")
      (node (ref "IC2") (pin "6") (pinfunction "O_6") (pintype "open_collector"))
      (node (ref "R14") (pin "1") (pinfunction "1_1") (pintype "passive"))
    )
    (net (code "204") (name "Net-(IC2D-O)") (class "Default")
      (node (ref "IC2") (pin "8") (pinfunction "O_8") (pintype "open_collector"))
      (node (ref "R16") (pin "1") (pinfunction "1_1") (pintype "passive"))
    )
    (net (code "205") (name "Net-(IC2E-O)") (class "Default")
      (node (ref "IC2") (pin "10") (pinfunction "O_10") (pintype "open_collector"))
      (node (ref "R17") (pin "1") (pinfunction "1_1") (pintype "passive"))
    )
    (net (code "206") (name "Net-(IC2F-O)") (class "Default")
      (node (ref "IC2") (pin "12") (pinfunction "O_12") (pintype "open_collector"))
      (node (ref "R18") (pin "1") (pinfunction "1_1") (pintype "passive"))
    )
    (net (code "207") (name "Net-(IC3A-O)") (class "Default")
      (node (ref "IC3") (pin "2") (pinfunction "O_2") (pintype "open_collector"))
      (node (ref "R3") (pin "1") (pinfunction "1_1") (pintype "passive"))
    )
    (net (code "208") (name "Net-(IC3B-O)") (class "Default")
      (node (ref "IC3") (pin "4") (pinfunction "O_4") (pintype "open_collector"))
      (node (ref "R2") (pin "1") (pinfunction "1_1") (pintype "passive"))
    )
    (net (code "209") (name "Net-(IC3C-O)") (class "Default")
      (node (ref "IC3") (pin "6") (pinfunction "O_6") (pintype "open_collector"))
      (node (ref "R1") (pin "1") (pinfunction "1_1") (pintype "passive"))
    )
    (net (code "210") (name "Net-(IC3D-O)") (class "Default")
      (node (ref "IC3") (pin "8") (pinfunction "O_8") (pintype "open_collector"))
      (node (ref "R5") (pin "1") (pinfunction "1_1") (pintype "passive"))
    )
    (net (code "211") (name "Net-(IC3E-O)") (class "Default")
      (node (ref "IC3") (pin "10") (pinfunction "O_10") (pintype "open_collector"))
      (node (ref "R4") (pin "1") (pinfunction "1_1") (pintype "passive"))
    )
    (net (code "212") (name "Net-(IC3F-O)") (class "Default")
      (node (ref "IC3") (pin "12") (pinfunction "O_12") (pintype "open_collector"))
      (node (ref "R7") (pin "1") (pinfunction "1_1") (pintype "passive"))
    )
    (net (code "213") (name "Net-(IC4A-O)") (class "Default")
      (node (ref "IC4") (pin "2") (pinfunction "O_2") (pintype "open_collector"))
      (node (ref "R19") (pin "1") (pinfunction "1_1") (pintype "passive"))
    )
    (net (code "214") (name "Net-(IC4B-O)") (class "Default")
      (node (ref "IC4") (pin "4") (pinfunction "O_4") (pintype "open_collector"))
      (node (ref "R20") (pin "1") (pinfunction "1_1") (pintype "passive"))
    )
    (net (code "215") (name "Net-(IC4C-O)") (class "Default")
      (node (ref "IC4") (pin "6") (pinfunction "O_6") (pintype "open_collector"))
      (node (ref "R21") (pin "1") (pinfunction "1_1") (pintype "passive"))
    )
    (net (code "216") (name "Net-(IC4D-O)") (class "Default")
      (node (ref "IC4") (pin "8") (pinfunction "O_8") (pintype "open_collector"))
      (node (ref "R23") (pin "1") (pinfunction "1_1") (pintype "passive"))
    )
    (net (code "217") (name "Net-(IC4E-O)") (class "Default")
      (node (ref "IC4") (pin "10") (pinfunction "O_10") (pintype "open_collector"))
      (node (ref "R22") (pin "1") (pinfunction "1_1") (pintype "passive"))
    )
    (net (code "218") (name "Net-(IC4F-O)") (class "Default")
      (node (ref "IC4") (pin "12") (pinfunction "O_12") (pintype "open_collector"))
      (node (ref "R25") (pin "1") (pinfunction "1_1") (pintype "passive"))
    )
    (net (code "219") (name "Net-(IC5A-O)") (class "Default")
      (node (ref "IC5") (pin "2") (pinfunction "O_2") (pintype "open_collector"))
      (node (ref "R27") (pin "1") (pinfunction "1_1") (pintype "passive"))
    )
    (net (code "220") (name "Net-(IC5B-O)") (class "Default")
      (node (ref "IC5") (pin "4") (pinfunction "O_4") (pintype "open_collector"))
      (node (ref "R26") (pin "1") (pinfunction "1_1") (pintype "passive"))
    )
    (net (code "221") (name "Net-(IC5C-O)") (class "Default")
      (node (ref "IC5") (pin "6") (pinfunction "O_6") (pintype "open_collector"))
      (node (ref "R24") (pin "1") (pinfunction "1_1") (pintype "passive"))
    )
    (net (code "222") (name "Net-(IC5D-O)") (class "Default")
      (node (ref "IC5") (pin "8") (pinfunction "O_8") (pintype "open_collector"))
      (node (ref "R28") (pin "1") (pinfunction "1_1") (pintype "passive"))
    )
    (net (code "223") (name "Net-(IC5E-O)") (class "Default")
      (node (ref "IC5") (pin "10") (pinfunction "O_10") (pintype "open_collector"))
      (node (ref "R29") (pin "1") (pinfunction "1_1") (pintype "passive"))
    )
    (net (code "224") (name "Net-(IC5F-O)") (class "Default")
      (node (ref "IC5") (pin "12") (pinfunction "O_12") (pintype "open_collector"))
      (node (ref "R30") (pin "1") (pinfunction "1_1") (pintype "passive"))
    )
    (net (code "225") (name "Net-(IC6A-I1)") (class "Default")
      (node (ref "IC6") (pin "2") (pinfunction "I1_2") (pintype "input"))
      (node (ref "IC6") (pin "6") (pinfunction "O_6") (pintype "output"))
      (node (ref "IC8") (pin "2") (pinfunction "I1_2") (pintype "input"))
    )
    (net (code "226") (name "Net-(IC6A-O)") (class "Default")
      (node (ref "IC6") (pin "3") (pinfunction "O_3") (pintype "output"))
      (node (ref "IC6") (pin "4") (pinfunction "I0_4") (pintype "input"))
    )
    (net (code "227") (name "Net-(IC6C-I1)") (class "Default")
      (node (ref "IC6") (pin "10") (pinfunction "I1_10") (pintype "input"))
      (node (ref "IC6") (pin "11") (pinfunction "O_11") (pintype "output"))
    )
    (net (code "228") (name "Net-(IC6C-O)") (class "Default")
      (node (ref "IC6") (pin "12") (pinfunction "I0_12") (pintype "input"))
      (node (ref "IC6") (pin "8") (pinfunction "O_8") (pintype "output"))
      (node (ref "IC7") (pin "13") (pinfunction "I1_13") (pintype "input"))
    )
    (net (code "229") (name "Net-(IC7A-I0)") (class "Default")
      (node (ref "IC7") (pin "1") (pinfunction "I0_1") (pintype "input"))
      (node (ref "R55") (pin "1") (pinfunction "1_1") (pintype "passive"))
      (node (ref "RUN") (pin "3") (pinfunction "S_3") (pintype "passive"))
    )
    (net (code "230") (name "Net-(IC7A-O)") (class "Default")
      (node (ref "IC7") (pin "3") (pinfunction "O_3") (pintype "output"))
      (node (ref "IC7") (pin "4") (pinfunction "I0_4") (pintype "input"))
    )
    (net (code "231") (name "Net-(IC7B-I1)") (class "Default")
      (node (ref "IC7") (pin "5") (pinfunction "I1_5") (pintype "input"))
      (node (ref "R54") (pin "1") (pinfunction "1_1") (pintype "passive"))
      (node (ref "RUN") (pin "1") (pinfunction "O_1") (pintype "passive"))
    )
    (net (code "232") (name "Net-(IC7C-I0)") (class "Default")
      (node (ref "IC7") (pin "10") (pinfunction "I1_10") (pintype "input"))
      (node (ref "IC7") (pin "11") (pinfunction "O_11") (pintype "output"))
      (node (ref "IC7") (pin "9") (pinfunction "I0_9") (pintype "input"))
    )
    (net (code "233") (name "Net-(IC8B-O)") (class "Default")
      (node (ref "IC8") (pin "6") (pinfunction "O_6") (pintype "output"))
      (node (ref "IC8") (pin "9") (pinfunction "I0_9") (pintype "input"))
    )
    (net (code "234") (name "Net-(IC8C-O)") (class "Default")
      (node (ref "IC8") (pin "12") (pinfunction "I0_12") (pintype "input"))
      (node (ref "IC8") (pin "8") (pinfunction "O_8") (pintype "output"))
    )
    (net (code "235") (name "Net-(IC10A-O)") (class "Default")
      (node (ref "IC10") (pin "2") (pinfunction "O_2") (pintype "open_collector"))
      (node (ref "R31") (pin "1") (pinfunction "1_1") (pintype "passive"))
    )
    (net (code "236") (name "Net-(IC10B-O)") (class "Default")
      (node (ref "IC10") (pin "4") (pinfunction "O_4") (pintype "open_collector"))
      (node (ref "R32") (pin "1") (pinfunction "1_1") (pintype "passive"))
    )
    (net (code "237") (name "Net-(IC10C-O)") (class "Default")
      (node (ref "IC10") (pin "6") (pinfunction "O_6") (pintype "open_collector"))
      (node (ref "R33") (pin "1") (pinfunction "1_1") (pintype "passive"))
    )
    (net (code "238") (name "Net-(IC10D-O)") (class "Default")
      (node (ref "IC10") (pin "8") (pinfunction "O_8") (pintype "open_collector"))
      (node (ref "R36") (pin "1") (pinfunction "1_1") (pintype "passive"))
    )
    (net (code "239") (name "Net-(IC10E-O)") (class "Default")
      (node (ref "IC10") (pin "10") (pinfunction "O_10") (pintype "open_collector"))
      (node (ref "R35") (pin "1") (pinfunction "1_1") (pintype "passive"))
    )
    (net (code "240") (name "Net-(IC10F-O)") (class "Default")
      (node (ref "IC10") (pin "12") (pinfunction "O_12") (pintype "open_collector"))
      (node (ref "R34") (pin "1") (pinfunction "1_1") (pintype "passive"))
    )
    (net (code "241") (name "Net-(IC11A-O)") (class "Default")
      (node (ref "IC11") (pin "2") (pinfunction "O_2") (pintype "open_collector"))
      (node (ref "R37") (pin "1") (pinfunction "1_1") (pintype "passive"))
    )
    (net (code "242") (name "Net-(IC11B-O)") (class "Default")
      (node (ref "IC11") (pin "4") (pinfunction "O_4") (pintype "open_collector"))
      (node (ref "R38") (pin "1") (pinfunction "1_1") (pintype "passive"))
    )
    (net (code "243") (name "Net-(IC11C-O)") (class "Default")
      (node (ref "IC11") (pin "6") (pinfunction "O_6") (pintype "open_collector"))
      (node (ref "R39") (pin "1") (pinfunction "1_1") (pintype "passive"))
    )
    (net (code "244") (name "Net-(IC11D-O)") (class "Default")
      (node (ref "IC11") (pin "8") (pinfunction "O_8") (pintype "open_collector"))
      (node (ref "R40") (pin "1") (pinfunction "1_1") (pintype "passive"))
    )
    (net (code "245") (name "Net-(IC11E-O)") (class "Default")
      (node (ref "IC11") (pin "10") (pinfunction "O_10") (pintype "open_collector"))
      (node (ref "R41") (pin "1") (pinfunction "1_1") (pintype "passive"))
    )
    (net (code "246") (name "Net-(IC11F-O)") (class "Default")
      (node (ref "IC11") (pin "12") (pinfunction "O_12") (pintype "open_collector"))
      (node (ref "R42") (pin "1") (pinfunction "1_1") (pintype "passive"))
    )
    (net (code "247") (name "Net-(IC12A-A)") (class "Default")
      (node (ref "IC12") (pin "5") (pinfunction "A_5") (pintype "input"))
      (node (ref "IC9") (pin "13") (pinfunction "I1_13") (pintype "input"))
      (node (ref "IC9") (pin "3") (pinfunction "O_3") (pintype "output"))
    )
    (net (code "248") (name "Net-(IC12A-C)") (class "Default")
      (node (ref "C1") (pin "1") (pinfunction "1_1") (pintype "passive"))
      (node (ref "IC12") (pin "1") (pinfunction "C_1") (pintype "input"))
    )
    (net (code "249") (name "Net-(IC12A-CLR)") (class "Default")
      (node (ref "IC12") (pin "13") (pinfunction "CLR_13") (pintype "input"))
      (node (ref "IC12") (pin "3") (pinfunction "CLR_3") (pintype "input"))
      (node (ref "R53") (pin "1") (pinfunction "1_1") (pintype "passive"))
    )
    (net (code "250") (name "Net-(IC12A-R{slash}C)") (class "Default")
      (node (ref "C1") (pin "2") (pinfunction "2_2") (pintype "passive"))
      (node (ref "IC12") (pin "2") (pinfunction "R/C_2") (pintype "input"))
      (node (ref "R51") (pin "1") (pinfunction "1_1") (pintype "passive"))
    )
    (net (code "251") (name "Net-(IC12A-~{Q})") (class "Default")
      (node (ref "IC12") (pin "7") (pinfunction "~{Q}_7") (pintype "output"))
      (node (ref "IC9") (pin "10") (pinfunction "I1_10") (pintype "input"))
      (node (ref "IC9") (pin "12") (pinfunction "I0_12") (pintype "input"))
      (node (ref "IC9") (pin "9") (pinfunction "I0_9") (pintype "input"))
    )
    (net (code "252") (name "Net-(IC12B-A)") (class "Default")
      (node (ref "IC12") (pin "11") (pinfunction "A_11") (pintype "input"))
      (node (ref "IC7") (pin "2") (pinfunction "I1_2") (pintype "input"))
      (node (ref "IC7") (pin "6") (pinfunction "O_6") (pintype "output"))
    )
    (net (code "253") (name "Net-(IC12B-B)") (class "Default")
      (node (ref "IC12") (pin "12") (pinfunction "B_12") (pintype "input"))
      (node (ref "IC8") (pin "3") (pinfunction "O_3") (pintype "output"))
      (node (ref "IC8") (pin "4") (pinfunction "I0_4") (pintype "input"))
    )
    (net (code "254") (name "Net-(IC12B-C)") (class "Default")
      (node (ref "C2") (pin "1") (pinfunction "1_1") (pintype "passive"))
      (node (ref "IC12") (pin "15") (pinfunction "C_15") (pintype "input"))
    )
    (net (code "255") (name "Net-(IC12B-Q)") (class "Default")
      (node (ref "IC12") (pin "10") (pinfunction "Q_10") (pintype "output"))
      (node (ref "IC8") (pin "5") (pinfunction "I1_5") (pintype "input"))
    )
    (net (code "256") (name "Net-(IC12B-R{slash}C)") (class "Default")
      (node (ref "C2") (pin "2") (pinfunction "2_2") (pintype "passive"))
      (node (ref "IC12") (pin "14") (pinfunction "R/C_14") (pintype "input"))
      (node (ref "R52") (pin "1") (pinfunction "1_1") (pintype "passive"))
    )
    (net (code "257") (name "Net-(LED1-C)") (class "Default")
      (node (ref "LED1") (pin "K") (pinfunction "C_K") (pintype "passive"))
      (node (ref "R1") (pin "2") (pinfunction "2_2") (pintype "passive"))
    )
    (net (code "258") (name "Net-(LED2-C)") (class "Default")
      (node (ref "LED2") (pin "K") (pinfunction "C_K") (pintype "passive"))
      (node (ref "R2") (pin "2") (pinfunction "2_2") (pintype "passive"))
    )
    (net (code "259") (name "Net-(LED3-C)") (class "Default")
      (node (ref "LED3") (pin "K") (pinfunction "C_K") (pintype "passive"))
      (node (ref "R3") (pin "2") (pinfunction "2_2") (pintype "passive"))
    )
    (net (code "260") (name "Net-(LED4-C)") (class "Default")
      (node (ref "LED4") (pin "K") (pinfunction "C_K") (pintype "passive"))
      (node (ref "R5") (pin "2") (pinfunction "2_2") (pintype "passive"))
    )
    (net (code "261") (name "Net-(LED5-C)") (class "Default")
      (node (ref "LED5") (pin "K") (pinfunction "C_K") (pintype "passive"))
      (node (ref "R4") (pin "2") (pinfunction "2_2") (pintype "passive"))
    )
    (net (code "262") (name "Net-(LED6-C)") (class "Default")
      (node (ref "LED6") (pin "K") (pinfunction "C_K") (pintype "passive"))
      (node (ref "R7") (pin "2") (pinfunction "2_2") (pintype "passive"))
    )
    (net (code "263") (name "Net-(LED7-C)") (class "Default")
      (node (ref "LED7") (pin "K") (pinfunction "C_K") (pintype "passive"))
      (node (ref "R6") (pin "2") (pinfunction "2_2") (pintype "passive"))
    )
    (net (code "264") (name "Net-(LED8-PadA)") (class "Default")
      (node (ref "LED8") (pin "A") (pinfunction "A_A") (pintype "passive"))
      (node (ref "R9") (pin "1") (pinfunction "1_1") (pintype "passive"))
    )
    (net (code "265") (name "Net-(LED9-PadA)") (class "Default")
      (node (ref "LED9") (pin "A") (pinfunction "A_A") (pintype "passive"))
      (node (ref "R8") (pin "1") (pinfunction "1_1") (pintype "passive"))
    )
    (net (code "266") (name "Net-(LED10-C)") (class "Default")
      (node (ref "LED10") (pin "K") (pinfunction "C_K") (pintype "passive"))
      (node (ref "R11") (pin "2") (pinfunction "2_2") (pintype "passive"))
    )
    (net (code "267") (name "Net-(LED11-C)") (class "Default")
      (node (ref "LED11") (pin "K") (pinfunction "C_K") (pintype "passive"))
      (node (ref "R10") (pin "2") (pinfunction "2_2") (pintype "passive"))
    )
    (net (code "268") (name "Net-(LED12-C)") (class "Default")
      (node (ref "LED12") (pin "K") (pinfunction "C_K") (pintype "passive"))
      (node (ref "R13") (pin "2") (pinfunction "2_2") (pintype "passive"))
    )
    (net (code "269") (name "Net-(LED13-C)") (class "Default")
      (node (ref "LED13") (pin "K") (pinfunction "C_K") (pintype "passive"))
      (node (ref "R12") (pin "2") (pinfunction "2_2") (pintype "passive"))
    )
    (net (code "270") (name "Net-(LED14-C)") (class "Default")
      (node (ref "LED14") (pin "K") (pinfunction "C_K") (pintype "passive"))
      (node (ref "R15") (pin "2") (pinfunction "2_2") (pintype "passive"))
    )
    (net (code "271") (name "Net-(LED15-C)") (class "Default")
      (node (ref "LED15") (pin "K") (pinfunction "C_K") (pintype "passive"))
      (node (ref "R14") (pin "2") (pinfunction "2_2") (pintype "passive"))
    )
    (net (code "272") (name "Net-(LED16-C)") (class "Default")
      (node (ref "LED16") (pin "K") (pinfunction "C_K") (pintype "passive"))
      (node (ref "R16") (pin "2") (pinfunction "2_2") (pintype "passive"))
    )
    (net (code "273") (name "Net-(LED17-C)") (class "Default")
      (node (ref "LED17") (pin "K") (pinfunction "C_K") (pintype "passive"))
      (node (ref "R17") (pin "2") (pinfunction "2_2") (pintype "passive"))
    )
    (net (code "274") (name "Net-(LED18-C)") (class "Default")
      (node (ref "LED18") (pin "K") (pinfunction "C_K") (pintype "passive"))
      (node (ref "R18") (pin "2") (pinfunction "2_2") (pintype "passive"))
    )
    (net (code "275") (name "Net-(LED19-C)") (class "Default")
      (node (ref "LED19") (pin "K") (pinfunction "C_K") (pintype "passive"))
      (node (ref "R19") (pin "2") (pinfunction "2_2") (pintype "passive"))
    )
    (net (code "276") (name "Net-(LED20-C)") (class "Default")
      (node (ref "LED20") (pin "K") (pinfunction "C_K") (pintype "passive"))
      (node (ref "R20") (pin "2") (pinfunction "2_2") (pintype "passive"))
    )
    (net (code "277") (name "Net-(LED21-C)") (class "Default")
      (node (ref "LED21") (pin "K") (pinfunction "C_K") (pintype "passive"))
      (node (ref "R21") (pin "2") (pinfunction "2_2") (pintype "passive"))
    )
    (net (code "278") (name "Net-(LED22-C)") (class "Default")
      (node (ref "LED22") (pin "K") (pinfunction "C_K") (pintype "passive"))
      (node (ref "R23") (pin "2") (pinfunction "2_2") (pintype "passive"))
    )
    (net (code "279") (name "Net-(LED23-C)") (class "Default")
      (node (ref "LED23") (pin "K") (pinfunction "C_K") (pintype "passive"))
      (node (ref "R22") (pin "2") (pinfunction "2_2") (pintype "passive"))
    )
    (net (code "280") (name "Net-(LED24-C)") (class "Default")
      (node (ref "LED24") (pin "K") (pinfunction "C_K") (pintype "passive"))
      (node (ref "R25") (pin "2") (pinfunction "2_2") (pintype "passive"))
    )
    (net (code "281") (name "Net-(LED25-C)") (class "Default")
      (node (ref "LED25") (pin "K") (pinfunction "C_K") (pintype "passive"))
      (node (ref "R24") (pin "2") (pinfunction "2_2") (pintype "passive"))
    )
    (net (code "282") (name "Net-(LED26-C)") (class "Default")
      (node (ref "LED26") (pin "K") (pinfunction "C_K") (pintype "passive"))
      (node (ref "R27") (pin "2") (pinfunction "2_2") (pintype "passive"))
    )
    (net (code "283") (name "Net-(LED27-C)") (class "Default")
      (node (ref "LED27") (pin "K") (pinfunction "C_K") (pintype "passive"))
      (node (ref "R26") (pin "2") (pinfunction "2_2") (pintype "passive"))
    )
    (net (code "284") (name "Net-(LED28-C)") (class "Default")
      (node (ref "LED28") (pin "K") (pinfunction "C_K") (pintype "passive"))
      (node (ref "R28") (pin "2") (pinfunction "2_2") (pintype "passive"))
    )
    (net (code "285") (name "Net-(LED29-C)") (class "Default")
      (node (ref "LED29") (pin "K") (pinfunction "C_K") (pintype "passive"))
      (node (ref "R29") (pin "2") (pinfunction "2_2") (pintype "passive"))
    )
    (net (code "286") (name "Net-(LED30-C)") (class "Default")
      (node (ref "LED30") (pin "K") (pinfunction "C_K") (pintype "passive"))
      (node (ref "R30") (pin "2") (pinfunction "2_2") (pintype "passive"))
    )
    (net (code "287") (name "Net-(LED31-C)") (class "Default")
      (node (ref "LED31") (pin "K") (pinfunction "C_K") (pintype "passive"))
      (node (ref "R32") (pin "2") (pinfunction "2_2") (pintype "passive"))
    )
    (net (code "288") (name "Net-(LED32-C)") (class "Default")
      (node (ref "LED32") (pin "K") (pinfunction "C_K") (pintype "passive"))
      (node (ref "R31") (pin "2") (pinfunction "2_2") (pintype "passive"))
    )
    (net (code "289") (name "Net-(LED33-C)") (class "Default")
      (node (ref "LED33") (pin "K") (pinfunction "C_K") (pintype "passive"))
      (node (ref "R33") (pin "2") (pinfunction "2_2") (pintype "passive"))
    )
    (net (code "290") (name "Net-(LED34-C)") (class "Default")
      (node (ref "LED34") (pin "K") (pinfunction "C_K") (pintype "passive"))
      (node (ref "R34") (pin "2") (pinfunction "2_2") (pintype "passive"))
    )
    (net (code "291") (name "Net-(LED35-C)") (class "Default")
      (node (ref "LED35") (pin "K") (pinfunction "C_K") (pintype "passive"))
      (node (ref "R35") (pin "2") (pinfunction "2_2") (pintype "passive"))
    )
    (net (code "292") (name "Net-(LED36-C)") (class "Default")
      (node (ref "LED36") (pin "K") (pinfunction "C_K") (pintype "passive"))
      (node (ref "R36") (pin "2") (pinfunction "2_2") (pintype "passive"))
    )
    (net (code "293") (name "Net-(LED37-C)") (class "Default")
      (node (ref "LED37") (pin "K") (pinfunction "C_K") (pintype "passive"))
      (node (ref "R37") (pin "2") (pinfunction "2_2") (pintype "passive"))
    )
    (net (code "294") (name "Net-(LED38-C)") (class "Default")
      (node (ref "LED38") (pin "K") (pinfunction "C_K") (pintype "passive"))
      (node (ref "R38") (pin "2") (pinfunction "2_2") (pintype "passive"))
    )
    (net (code "295") (name "Net-(LED39-C)") (class "Default")
      (node (ref "LED39") (pin "K") (pinfunction "C_K") (pintype "passive"))
      (node (ref "R39") (pin "2") (pinfunction "2_2") (pintype "passive"))
    )
    (net (code "296") (name "Net-(LED40-C)") (class "Default")
      (node (ref "LED40") (pin "K") (pinfunction "C_K") (pintype "passive"))
      (node (ref "R40") (pin "2") (pinfunction "2_2") (pintype "passive"))
    )
    (net (code "297") (name "Net-(LED41-C)") (class "Default")
      (node (ref "LED41") (pin "K") (pinfunction "C_K") (pintype "passive"))
      (node (ref "R41") (pin "2") (pinfunction "2_2") (pintype "passive"))
    )
    (net (code "298") (name "Net-(LED42-C)") (class "Default")
      (node (ref "LED42") (pin "K") (pinfunction "C_K") (pintype "passive"))
      (node (ref "R42") (pin "2") (pinfunction "2_2") (pintype "passive"))
    )
    (net (code "299") (name "Net-(SLOW-O)") (class "Default")
      (node (ref "C4") (pin "-") (pinfunction "-_-") (pintype "passive"))
      (node (ref "SLOW") (pin "1") (pinfunction "O_1") (pintype "passive"))
      (node (ref "SLOW") (pin "2") (pinfunction "P_2") (pintype "passive"))
    )
    (net (code "300") (name "Net-(SW0-O)") (class "Default")
      (node (ref "R50") (pin "1") (pinfunction "1_1") (pintype "passive"))
      (node (ref "SR0") (pin "1") (pinfunction "1_1") (pintype "passive"))
      (node (ref "SW0") (pin "1") (pinfunction "O_1") (pintype "passive"))
      (node (ref "SW0") (pin "2") (pinfunction "P_2") (pintype "passive"))
    )
    (net (code "301") (name "Net-(SW1-O)") (class "Default")
      (node (ref "R49") (pin "1") (pinfunction "1_1") (pintype "passive"))
      (node (ref "SR1") (pin "1") (pinfunction "1_1") (pintype "passive"))
      (node (ref "SW1") (pin "1") (pinfunction "O_1") (pintype "passive"))
      (node (ref "SW1") (pin "2") (pinfunction "P_2") (pintype "passive"))
    )
    (net (code "302") (name "Net-(SW2-O)") (class "Default")
      (node (ref "R48") (pin "1") (pinfunction "1_1") (pintype "passive"))
      (node (ref "SR2") (pin "1") (pinfunction "1_1") (pintype "passive"))
      (node (ref "SW2") (pin "1") (pinfunction "O_1") (pintype "passive"))
      (node (ref "SW2") (pin "2") (pinfunction "P_2") (pintype "passive"))
    )
    (net (code "303") (name "Net-(SW3-O)") (class "Default")
      (node (ref "R47") (pin "1") (pinfunction "1_1") (pintype "passive"))
      (node (ref "SR3") (pin "1") (pinfunction "1_1") (pintype "passive"))
      (node (ref "SW3") (pin "1") (pinfunction "O_1") (pintype "passive"))
      (node (ref "SW3") (pin "2") (pinfunction "P_2") (pintype "passive"))
    )
    (net (code "304") (name "Net-(SW4-O)") (class "Default")
      (node (ref "R46") (pin "1") (pinfunction "1_1") (pintype "passive"))
      (node (ref "SR4") (pin "1") (pinfunction "1_1") (pintype "passive"))
      (node (ref "SW4") (pin "1") (pinfunction "O_1") (pintype "passive"))
      (node (ref "SW4") (pin "2") (pinfunction "P_2") (pintype "passive"))
    )
    (net (code "305") (name "Net-(SW5-O)") (class "Default")
      (node (ref "R45") (pin "1") (pinfunction "1_1") (pintype "passive"))
      (node (ref "SR5") (pin "1") (pinfunction "1_1") (pintype "passive"))
      (node (ref "SW5") (pin "1") (pinfunction "O_1") (pintype "passive"))
      (node (ref "SW5") (pin "2") (pinfunction "P_2") (pintype "passive"))
    )
    (net (code "306") (name "Net-(SW6-O)") (class "Default")
      (node (ref "R44") (pin "1") (pinfunction "1_1") (pintype "passive"))
      (node (ref "SR6") (pin "1") (pinfunction "1_1") (pintype "passive"))
      (node (ref "SW6") (pin "1") (pinfunction "O_1") (pintype "passive"))
      (node (ref "SW6") (pin "2") (pinfunction "P_2") (pintype "passive"))
    )
    (net (code "307") (name "Net-(SW7-O)") (class "Default")
      (node (ref "R43") (pin "1") (pinfunction "1_1") (pintype "passive"))
      (node (ref "SR7") (pin "1") (pinfunction "1_1") (pintype "passive"))
      (node (ref "SW7") (pin "1") (pinfunction "O_1") (pintype "passive"))
      (node (ref "SW7") (pin "2") (pinfunction "P_2") (pintype "passive"))
    )
    (net (code "308") (name "OPR") (class "Default")
      (node (ref "IC10") (pin "1") (pinfunction "I_1") (pintype "input"))
      (node (ref "OPR") (pin "1") (pinfunction "1_1") (pintype "passive"))
    )
    (net (code "309") (name "PC0") (class "Default")
      (node (ref "IC5") (pin "11") (pinfunction "I_11") (pintype "input"))
      (node (ref "PC0") (pin "1") (pinfunction "1_1") (pintype "passive"))
    )
    (net (code "310") (name "PC1") (class "Default")
      (node (ref "IC5") (pin "1") (pinfunction "I_1") (pintype "input"))
      (node (ref "PC1") (pin "1") (pinfunction "1_1") (pintype "passive"))
    )
    (net (code "311") (name "PC2") (class "Default")
      (node (ref "IC5") (pin "5") (pinfunction "I_5") (pintype "input"))
      (node (ref "PC2") (pin "1") (pinfunction "1_1") (pintype "passive"))
    )
    (net (code "312") (name "PC3") (class "Default")
      (node (ref "IC4") (pin "11") (pinfunction "I_11") (pintype "input"))
      (node (ref "PC3") (pin "1") (pinfunction "1_1") (pintype "passive"))
    )
    (net (code "313") (name "PC4") (class "Default")
      (node (ref "IC4") (pin "5") (pinfunction "I_5") (pintype "input"))
      (node (ref "PC4") (pin "1") (pinfunction "1_1") (pintype "passive"))
    )
    (net (code "314") (name "PC5") (class "Default")
      (node (ref "IC2") (pin "11") (pinfunction "I_11") (pintype "input"))
      (node (ref "PC5") (pin "1") (pinfunction "1_1") (pintype "passive"))
    )
    (net (code "315") (name "PC6") (class "Default")
      (node (ref "IC2") (pin "13") (pinfunction "I_13") (pintype "input"))
      (node (ref "PC6") (pin "1") (pinfunction "1_1") (pintype "passive"))
    )
    (net (code "316") (name "TAD") (class "Default")
      (node (ref "IC11") (pin "1") (pinfunction "I_1") (pintype "input"))
      (node (ref "TAD") (pin "1") (pinfunction "1_1") (pintype "passive"))
    )
    (net (code "317") (name "VCC") (class "Default")
      (node (ref "C6") (pin "1") (pinfunction "1_1") (pintype "passive"))
      (node (ref "C7") (pin "1") (pinfunction "1_1") (pintype "passive"))
      (node (ref "LED1") (pin "A") (pinfunction "A_A") (pintype "passive"))
      (node (ref "LED10") (pin "A") (pinfunction "A_A") (pintype "passive"))
      (node (ref "LED11") (pin "A") (pinfunction "A_A") (pintype "passive"))
      (node (ref "LED12") (pin "A") (pinfunction "A_A") (pintype "passive"))
      (node (ref "LED13") (pin "A") (pinfunction "A_A") (pintype "passive"))
      (node (ref "LED14") (pin "A") (pinfunction "A_A") (pintype "passive"))
      (node (ref "LED15") (pin "A") (pinfunction "A_A") (pintype "passive"))
      (node (ref "LED16") (pin "A") (pinfunction "A_A") (pintype "passive"))
      (node (ref "LED17") (pin "A") (pinfunction "A_A") (pintype "passive"))
      (node (ref "LED18") (pin "A") (pinfunction "A_A") (pintype "passive"))
      (node (ref "LED19") (pin "A") (pinfunction "A_A") (pintype "passive"))
      (node (ref "LED2") (pin "A") (pinfunction "A_A") (pintype "passive"))
      (node (ref "LED20") (pin "A") (pinfunction "A_A") (pintype "passive"))
      (node (ref "LED21") (pin "A") (pinfunction "A_A") (pintype "passive"))
      (node (ref "LED22") (pin "A") (pinfunction "A_A") (pintype "passive"))
      (node (ref "LED23") (pin "A") (pinfunction "A_A") (pintype "passive"))
      (node (ref "LED24") (pin "A") (pinfunction "A_A") (pintype "passive"))
      (node (ref "LED25") (pin "A") (pinfunction "A_A") (pintype "passive"))
      (node (ref "LED26") (pin "A") (pinfunction "A_A") (pintype "passive"))
      (node (ref "LED27") (pin "A") (pinfunction "A_A") (pintype "passive"))
      (node (ref "LED28") (pin "A") (pinfunction "A_A") (pintype "passive"))
      (node (ref "LED29") (pin "A") (pinfunction "A_A") (pintype "passive"))
      (node (ref "LED3") (pin "A") (pinfunction "A_A") (pintype "passive"))
      (node (ref "LED30") (pin "A") (pinfunction "A_A") (pintype "passive"))
      (node (ref "LED31") (pin "A") (pinfunction "A_A") (pintype "passive"))
      (node (ref "LED32") (pin "A") (pinfunction "A_A") (pintype "passive"))
      (node (ref "LED33") (pin "A") (pinfunction "A_A") (pintype "passive"))
      (node (ref "LED34") (pin "A") (pinfunction "A_A") (pintype "passive"))
      (node (ref "LED35") (pin "A") (pinfunction "A_A") (pintype "passive"))
      (node (ref "LED36") (pin "A") (pinfunction "A_A") (pintype "passive"))
      (node (ref "LED37") (pin "A") (pinfunction "A_A") (pintype "passive"))
      (node (ref "LED38") (pin "A") (pinfunction "A_A") (pintype "passive"))
      (node (ref "LED39") (pin "A") (pinfunction "A_A") (pintype "passive"))
      (node (ref "LED4") (pin "A") (pinfunction "A_A") (pintype "passive"))
      (node (ref "LED40") (pin "A") (pinfunction "A_A") (pintype "passive"))
      (node (ref "LED41") (pin "A") (pinfunction "A_A") (pintype "passive"))
      (node (ref "LED42") (pin "A") (pinfunction "A_A") (pintype "passive"))
      (node (ref "LED5") (pin "A") (pinfunction "A_A") (pintype "passive"))
      (node (ref "LED6") (pin "A") (pinfunction "A_A") (pintype "passive"))
      (node (ref "LED7") (pin "A") (pinfunction "A_A") (pintype "passive"))
      (node (ref "R43") (pin "2") (pinfunction "2_2") (pintype "passive"))
      (node (ref "R44") (pin "2") (pinfunction "2_2") (pintype "passive"))
      (node (ref "R45") (pin "2") (pinfunction "2_2") (pintype "passive"))
      (node (ref "R46") (pin "2") (pinfunction "2_2") (pintype "passive"))
      (node (ref "R47") (pin "2") (pinfunction "2_2") (pintype "passive"))
      (node (ref "R48") (pin "2") (pinfunction "2_2") (pintype "passive"))
      (node (ref "R49") (pin "2") (pinfunction "2_2") (pintype "passive"))
      (node (ref "R50") (pin "2") (pinfunction "2_2") (pintype "passive"))
      (node (ref "R51") (pin "2") (pinfunction "2_2") (pintype "passive"))
      (node (ref "R52") (pin "2") (pinfunction "2_2") (pintype "passive"))
      (node (ref "R53") (pin "2") (pinfunction "2_2") (pintype "passive"))
      (node (ref "R54") (pin "2") (pinfunction "2_2") (pintype "passive"))
      (node (ref "R55") (pin "2") (pinfunction "2_2") (pintype "passive"))
      (node (ref "R56") (pin "2") (pinfunction "2_2") (pintype "passive"))
      (node (ref "R57") (pin "2") (pinfunction "2_2") (pintype "passive"))
      (node (ref "R58") (pin "2") (pinfunction "2_2") (pintype "passive"))
      (node (ref "R59") (pin "2") (pinfunction "2_2") (pintype "passive"))
      (node (ref "R60") (pin "2") (pinfunction "2_2") (pintype "passive"))
      (node (ref "R61") (pin "2") (pinfunction "2_2") (pintype "passive"))
      (node (ref "R62") (pin "2") (pinfunction "2_2") (pintype "passive"))
      (node (ref "R8") (pin "2") (pinfunction "2_2") (pintype "passive"))
      (node (ref "R9") (pin "2") (pinfunction "2_2") (pintype "passive"))
      (node (ref "VCC") (pin "1") (pinfunction "1_1") (pintype "passive"))
    )
    (net (code "318") (name "unconnected-(E8/P-2-Pad7)") (class "Default")
      (node (ref "E8/P-2") (pin "7") (pinfunction "7_7") (pintype "passive"))
    )
    (net (code "319") (name "unconnected-(E8/P-2-Pad14)") (class "Default")
      (node (ref "E8/P-2") (pin "14") (pinfunction "14_14") (pintype "passive"))
    )
    (net (code "320") (name "unconnected-(E8/P-2-Pad15)") (class "Default")
      (node (ref "E8/P-2") (pin "15") (pinfunction "15_15") (pintype "passive"))
    )
    (net (code "321") (name "unconnected-(E8/P-2-Pad16)") (class "Default")
      (node (ref "E8/P-2") (pin "16") (pinfunction "16_16") (pintype "passive"))
    )
    (net (code "322") (name "unconnected-(E8/P-Pad29)") (class "Default")
      (node (ref "E8/P") (pin "29") (pinfunction "29_29") (pintype "passive"))
    )
    (net (code "323") (name "unconnected-(IC12A-Q-Pad6)") (class "Default")
      (node (ref "IC12") (pin "6") (pinfunction "Q_6") (pintype "output"))
    )
    (net (code "324") (name "unconnected-(R65-Pad1)") (class "Default")
      (node (ref "R65") (pin "1") (pinfunction "1_1") (pintype "passive"))
    )
    (net (code "325") (name "unconnected-(R66-Pad1)") (class "Default")
      (node (ref "R66") (pin "1") (pinfunction "1_1") (pintype "passive"))
    )
    (net (code "326") (name "~{CAND}") (class "Default")
      (node (ref "!CAND") (pin "1") (pinfunction "1_1") (pintype "passive"))
      (node (ref "E8/A-2") (pin "1") (pinfunction "1_1") (pintype "passive"))
      (node (ref "E8/D-2") (pin "1") (pinfunction "1_1") (pintype "passive"))
    )
    (net (code "327") (name "~{CCNCL_DEP_EX}") (class "Default")
      (node (ref "!CCNCL_DEP_EX") (pin "1") (pinfunction "1_1") (pintype "passive"))
    )
    (net (code "328") (name "~{CDCA}") (class "Default")
      (node (ref "!CDCA") (pin "1") (pinfunction "1_1") (pintype "passive"))
      (node (ref "E8/A-2") (pin "3") (pinfunction "3_3") (pintype "passive"))
      (node (ref "E8/D-2") (pin "4") (pinfunction "4_4") (pintype "passive"))
    )
    (net (code "329") (name "~{CDEFER}") (class "Default")
      (node (ref "!CDEFER") (pin "1") (pinfunction "1_1") (pintype "passive"))
    )
    (net (code "330") (name "~{CDEP_EX}") (class "Default")
      (node (ref "!CDEP_EX") (pin "1") (pinfunction "1_1") (pintype "passive"))
      (node (ref "E8/T") (pin "6") (pinfunction "6_6") (pintype "passive"))
    )
    (net (code "331") (name "~{CDEP}") (class "Default")
      (node (ref "!CDEP") (pin "1") (pinfunction "1_1") (pintype "passive"))
    )
    (net (code "332") (name "~{CEXEC}") (class "Default")
      (node (ref "!CEXEC") (pin "1") (pinfunction "1_1") (pintype "passive"))
    )
    (net (code "333") (name "~{CFETCH}") (class "Default")
      (node (ref "!CFETCH") (pin "1") (pinfunction "1_1") (pintype "passive"))
    )
    (net (code "334") (name "~{CHLT}") (class "Default")
      (node (ref "!CHLT") (pin "1") (pinfunction "1_1") (pintype "passive"))
      (node (ref "E8/D") (pin "24") (pinfunction "24_24") (pintype "passive"))
    )
    (net (code "335") (name "~{CIOT}") (class "Default")
      (node (ref "!CIOT") (pin "1") (pinfunction "1_1") (pintype "passive"))
      (node (ref "E8/D-2") (pin "7") (pinfunction "7_7") (pintype "passive"))
    )
    (net (code "336") (name "~{CISZ}") (class "Default")
      (node (ref "!CISZ") (pin "1") (pinfunction "1_1") (pintype "passive"))
      (node (ref "E8/D-2") (pin "3") (pinfunction "3_3") (pintype "passive"))
      (node (ref "E8/M-2") (pin "3") (pinfunction "3_3") (pintype "passive"))
      (node (ref "E8/P-2") (pin "3") (pinfunction "3_3") (pintype "passive"))
    )
    (net (code "337") (name "~{CJMP}") (class "Default")
      (node (ref "!CJMP") (pin "1") (pinfunction "1_1") (pintype "passive"))
      (node (ref "E8/D-2") (pin "6") (pinfunction "6_6") (pintype "passive"))
    )
    (net (code "338") (name "~{CJMS}") (class "Default")
      (node (ref "!CJMS") (pin "1") (pinfunction "1_1") (pintype "passive"))
      (node (ref "E8/D-2") (pin "5") (pinfunction "5_5") (pintype "passive"))
      (node (ref "E8/P-2") (pin "4") (pinfunction "4_4") (pintype "passive"))
    )
    (net (code "339") (name "~{CLA1}") (class "Default")
      (node (ref "!CLA1") (pin "1") (pinfunction "1_1") (pintype "passive"))
    )
    (net (code "340") (name "~{CLOCK-ID0}") (class "Default")
      (node (ref "!CLOCK-ID0") (pin "1") (pinfunction "1_1") (pintype "passive"))
      (node (ref "E8/10T-2") (pin "16") (pinfunction "16_16") (pintype "passive"))
    )
    (net (code "341") (name "~{CLOCK-ID1}") (class "Default")
      (node (ref "!CLOCK-ID1") (pin "1") (pinfunction "1_1") (pintype "passive"))
      (node (ref "E8/10T-2") (pin "12") (pinfunction "12_12") (pintype "passive"))
    )
    (net (code "342") (name "~{CLOCK-OD0}") (class "Default")
      (node (ref "!CLOCK-OD0") (pin "1") (pinfunction "1_1") (pintype "passive"))
      (node (ref "E8/10T-2") (pin "8") (pinfunction "8_8") (pintype "passive"))
    )
    (net (code "343") (name "~{CLOCK-OD1}") (class "Default")
      (node (ref "!CLOCK-OD1") (pin "1") (pinfunction "1_1") (pintype "passive"))
      (node (ref "E8/10T-2") (pin "4") (pinfunction "4_4") (pintype "passive"))
    )
    (net (code "344") (name "~{CNCL_DEP_EX}") (class "Default")
      (node (ref "!CNCL_DEP_EX") (pin "1") (pinfunction "1_1") (pintype "passive"))
      (node (ref "IC8") (pin "13") (pinfunction "I1_13") (pintype "input"))
    )
    (net (code "345") (name "~{COPR}") (class "Default")
      (node (ref "!COPR") (pin "1") (pinfunction "1_1") (pintype "passive"))
      (node (ref "E8/D-2") (pin "8") (pinfunction "8_8") (pintype "passive"))
    )
    (net (code "346") (name "~{CRUN_CMD}") (class "Default")
      (node (ref "!CRUN_CMD") (pin "1") (pinfunction "1_1") (pintype "passive"))
      (node (ref "E8/T") (pin "4") (pinfunction "4_4") (pintype "passive"))
    )
    (net (code "347") (name "~{CRUN}") (class "Default")
      (node (ref "!CRUN") (pin "1") (pinfunction "1_1") (pintype "passive"))
    )
    (net (code "348") (name "~{CTAD}") (class "Default")
      (node (ref "!CTAD") (pin "1") (pinfunction "1_1") (pintype "passive"))
      (node (ref "E8/A-2") (pin "2") (pinfunction "2_2") (pintype "passive"))
      (node (ref "E8/D-2") (pin "2") (pinfunction "2_2") (pintype "passive"))
      (node (ref "E8/M-2") (pin "2") (pinfunction "2_2") (pintype "passive"))
      (node (ref "E8/P-2") (pin "2") (pinfunction "2_2") (pintype "passive"))
    )
    (net (code "349") (name "~{DEFER}") (class "Default")
      (node (ref "!DEFER") (pin "1") (pinfunction "1_1") (pintype "passive"))
      (node (ref "IC11") (pin "13") (pinfunction "I_13") (pintype "input"))
    )
    (net (code "350") (name "~{DEPOSIT}") (class "Default")
      (node (ref "!DEPOSIT") (pin "1") (pinfunction "1_1") (pintype "passive"))
      (node (ref "IC7") (pin "8") (pinfunction "O_8") (pintype "output"))
      (node (ref "IC8") (pin "1") (pinfunction "I0_1") (pintype "input"))
    )
    (net (code "351") (name "~{DEP_EX}") (class "Default")
      (node (ref "!DEP_EX") (pin "1") (pinfunction "1_1") (pintype "passive"))
      (node (ref "IC8") (pin "10") (pinfunction "I1_10") (pintype "input"))
      (node (ref "IC8") (pin "11") (pinfunction "O_11") (pintype "output"))
    )
    (net (code "352") (name "~{EXEC}") (class "Default")
      (node (ref "!EXEC") (pin "1") (pinfunction "1_1") (pintype "passive"))
      (node (ref "IC11") (pin "5") (pinfunction "I_5") (pintype "input"))
    )
    (net (code "353") (name "~{EXT_DEP}") (class "Default")
      (node (ref "!EXT_DEP") (pin "1") (pinfunction "1_1") (pintype "passive"))
      (node (ref "C3") (pin "1") (pinfunction "1_1") (pintype "passive"))
      (node (ref "IC7") (pin "12") (pinfunction "I0_12") (pintype "input"))
      (node (ref "R56") (pin "1") (pinfunction "1_1") (pintype "passive"))
    )
    (net (code "354") (name "~{EXT_LA}") (class "Default")
      (node (ref "!EXT_LA") (pin "1") (pinfunction "1_1") (pintype "passive"))
      (node (ref "C5") (pin "1") (pinfunction "1_1") (pintype "passive"))
      (node (ref "IC9") (pin "1") (pinfunction "I0_1") (pintype "input"))
      (node (ref "IC9") (pin "2") (pinfunction "I1_2") (pintype "input"))
      (node (ref "LA") (pin "1") (pinfunction "O_1") (pintype "passive"))
      (node (ref "R62") (pin "1") (pinfunction "1_1") (pintype "passive"))
    )
    (net (code "355") (name "~{FETCH}") (class "Default")
      (node (ref "!FETCH") (pin "1") (pinfunction "1_1") (pintype "passive"))
      (node (ref "IC11") (pin "11") (pinfunction "I_11") (pintype "input"))
    )
    (net (code "356") (name "~{FLAG-ID0}") (class "Default")
      (node (ref "!FLAG-ID0") (pin "1") (pinfunction "1_1") (pintype "passive"))
      (node (ref "E8/10T-2") (pin "14") (pinfunction "14_14") (pintype "passive"))
    )
    (net (code "357") (name "~{FLAG-ID1}") (class "Default")
      (node (ref "!FLAG-ID1") (pin "1") (pinfunction "1_1") (pintype "passive"))
      (node (ref "E8/10T-2") (pin "10") (pinfunction "10_10") (pintype "passive"))
    )
    (net (code "358") (name "~{FLAG-OD0}") (class "Default")
      (node (ref "!FLAG-OD0") (pin "1") (pinfunction "1_1") (pintype "passive"))
      (node (ref "E8/10T-2") (pin "6") (pinfunction "6_6") (pintype "passive"))
    )
    (net (code "359") (name "~{FLAG-OD1}") (class "Default")
      (node (ref "!FLAG-OD1") (pin "1") (pinfunction "1_1") (pintype "passive"))
      (node (ref "E8/10T-2") (pin "2") (pinfunction "2_2") (pintype "passive"))
    )
    (net (code "360") (name "~{HLT}") (class "Default")
      (node (ref "!HLT") (pin "1") (pinfunction "1_1") (pintype "passive"))
      (node (ref "IC9") (pin "5") (pinfunction "I1_5") (pintype "input"))
    )
    (net (code "361") (name "~{LA1}") (class "Default")
      (node (ref "!LA1") (pin "1") (pinfunction "1_1") (pintype "passive"))
      (node (ref "IC9") (pin "11") (pinfunction "O_11") (pintype "output"))
    )
    (net (code "362") (name "~{RESET-ID0}") (class "Default")
      (node (ref "!RESET-ID0") (pin "1") (pinfunction "1_1") (pintype "passive"))
      (node (ref "E8/10T-2") (pin "15") (pinfunction "15_15") (pintype "passive"))
    )
    (net (code "363") (name "~{RESET-ID1}") (class "Default")
      (node (ref "!RESET-ID1") (pin "1") (pinfunction "1_1") (pintype "passive"))
      (node (ref "E8/10T-2") (pin "11") (pinfunction "11_11") (pintype "passive"))
    )
    (net (code "364") (name "~{RESET-OD0}") (class "Default")
      (node (ref "!RESET-OD0") (pin "1") (pinfunction "1_1") (pintype "passive"))
      (node (ref "E8/10T-2") (pin "7") (pinfunction "7_7") (pintype "passive"))
    )
    (net (code "365") (name "~{RESET-OD1}") (class "Default")
      (node (ref "!RESET-OD1") (pin "1") (pinfunction "1_1") (pintype "passive"))
      (node (ref "E8/10T-2") (pin "3") (pinfunction "3_3") (pintype "passive"))
    )
    (net (code "366") (name "~{RUN_CMD}") (class "Default")
      (node (ref "!RUN_CMD") (pin "1") (pinfunction "1_1") (pintype "passive"))
      (node (ref "IC12") (pin "9") (pinfunction "~{Q}_9") (pintype "output"))
    )
    (net (code "367") (name "~{RUN}") (class "Default")
      (node (ref "!RUN") (pin "1") (pinfunction "1_1") (pintype "passive"))
      (node (ref "IC11") (pin "9") (pinfunction "I_9") (pintype "input"))
    )
  )
)
